# DIY_Keyboard_V1_2.net
KiCad netlist of a schematic drawn in EAGLE
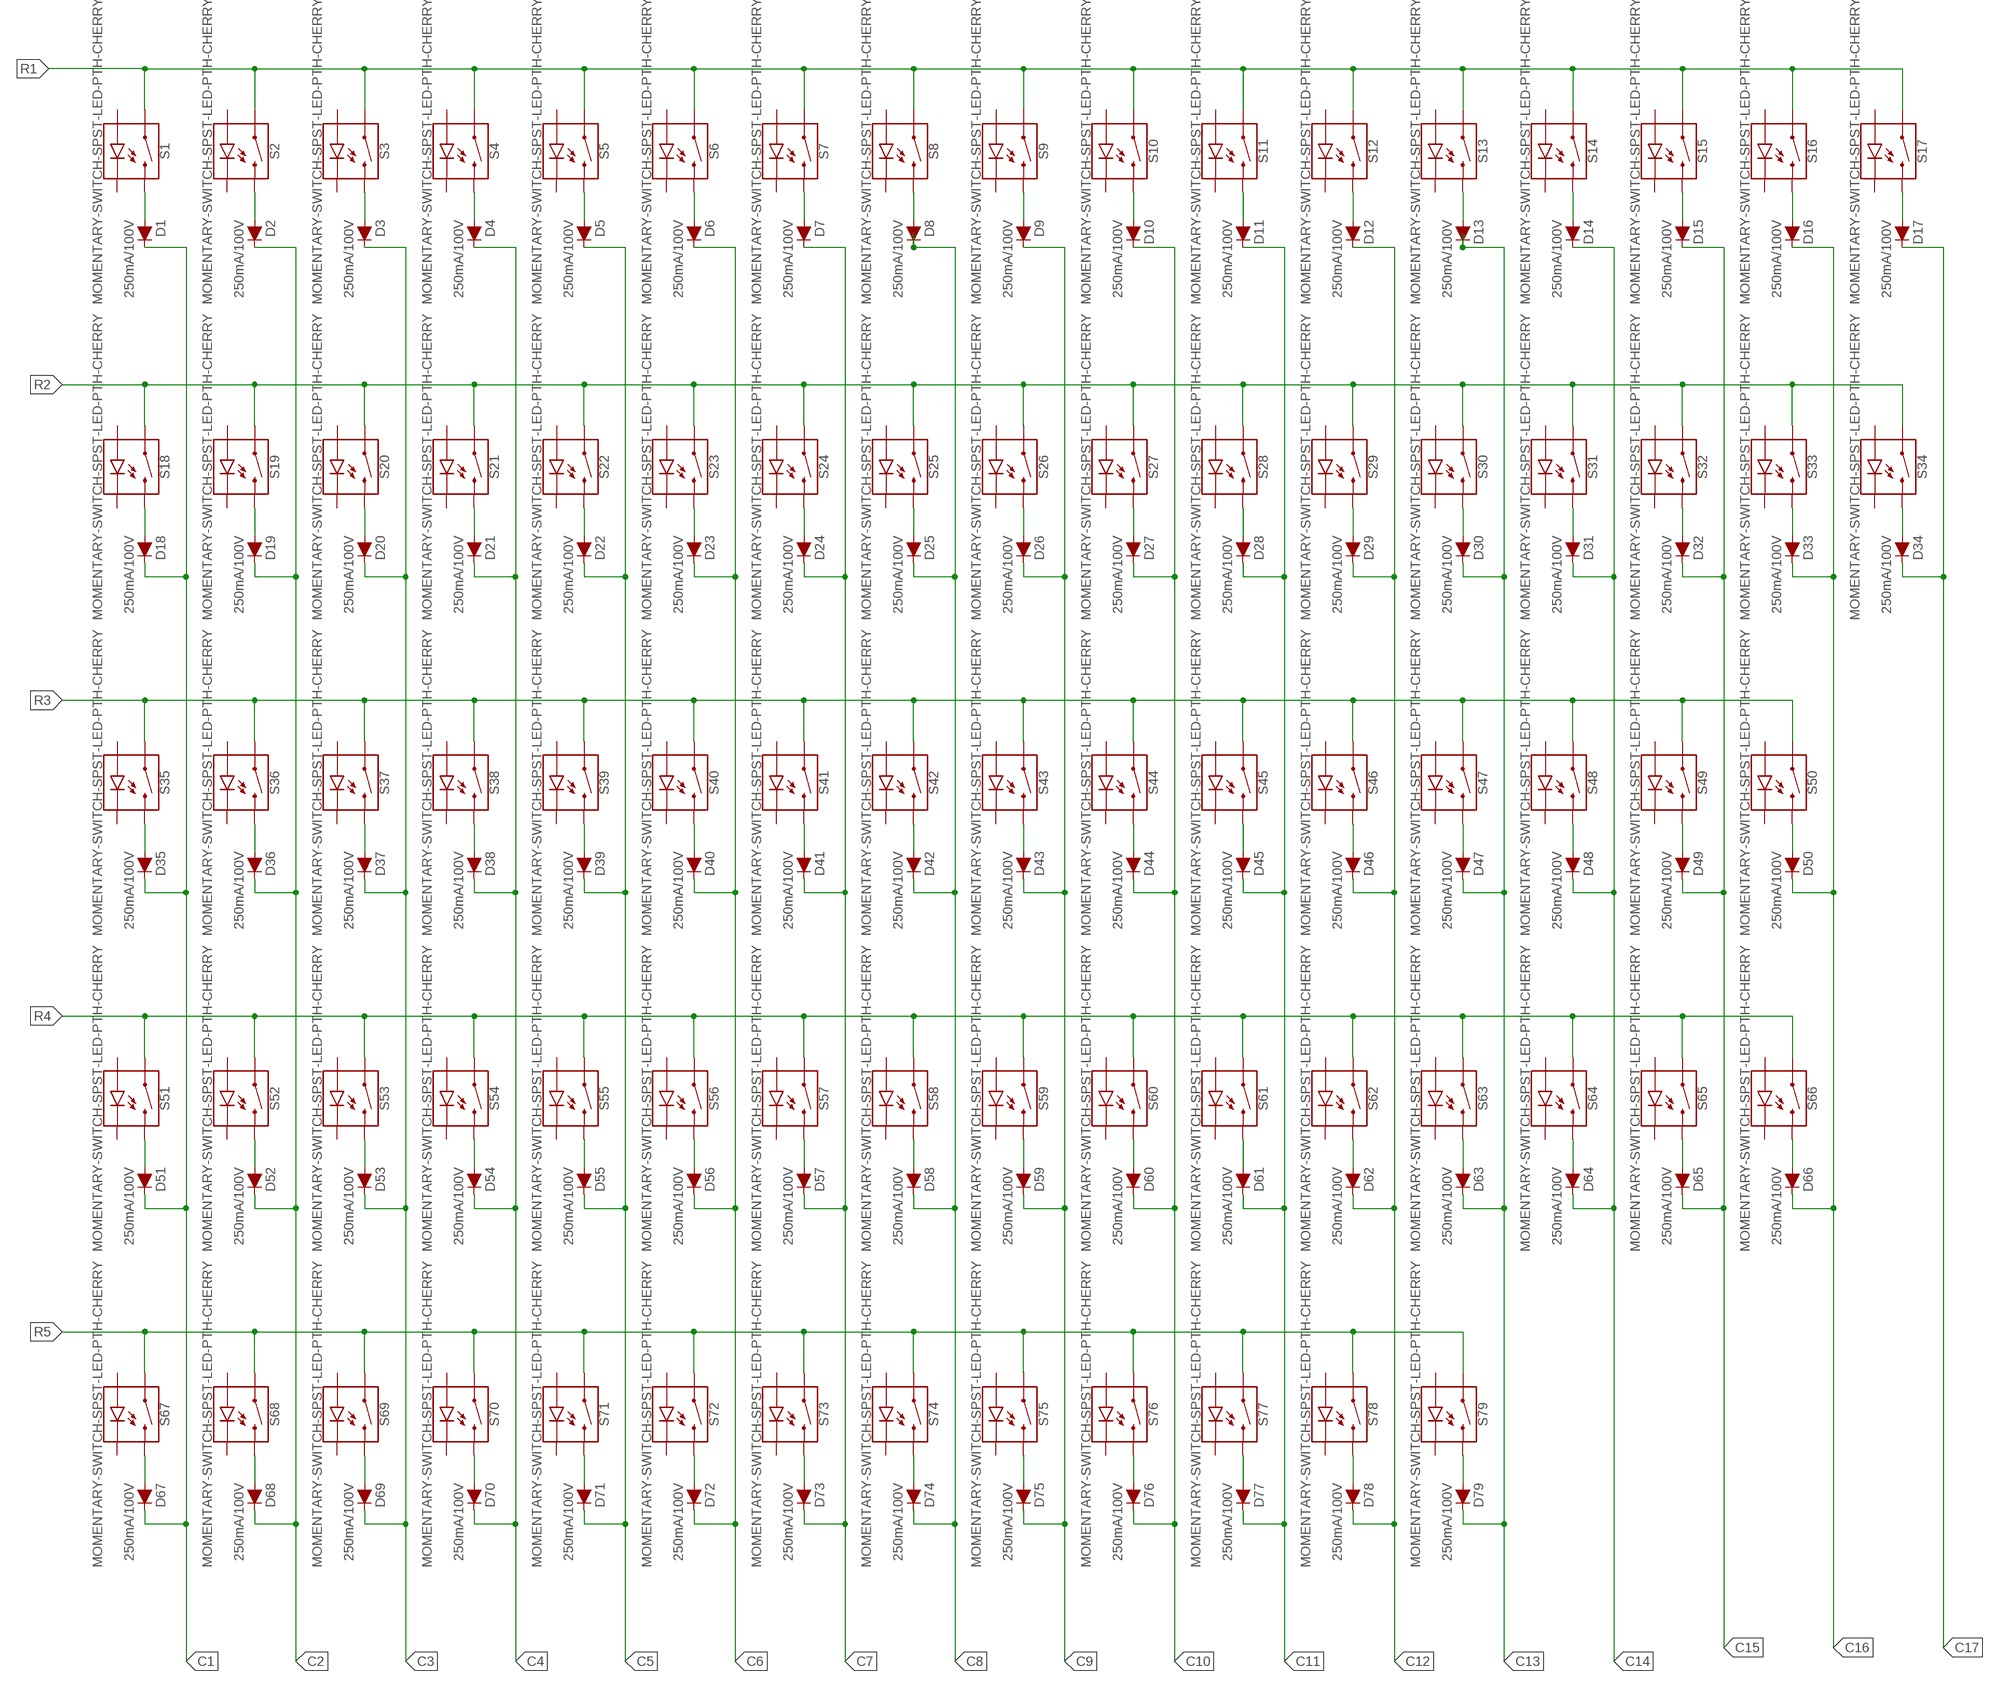
[diagram p0: schematic, sheet 1, part 1 of 2]
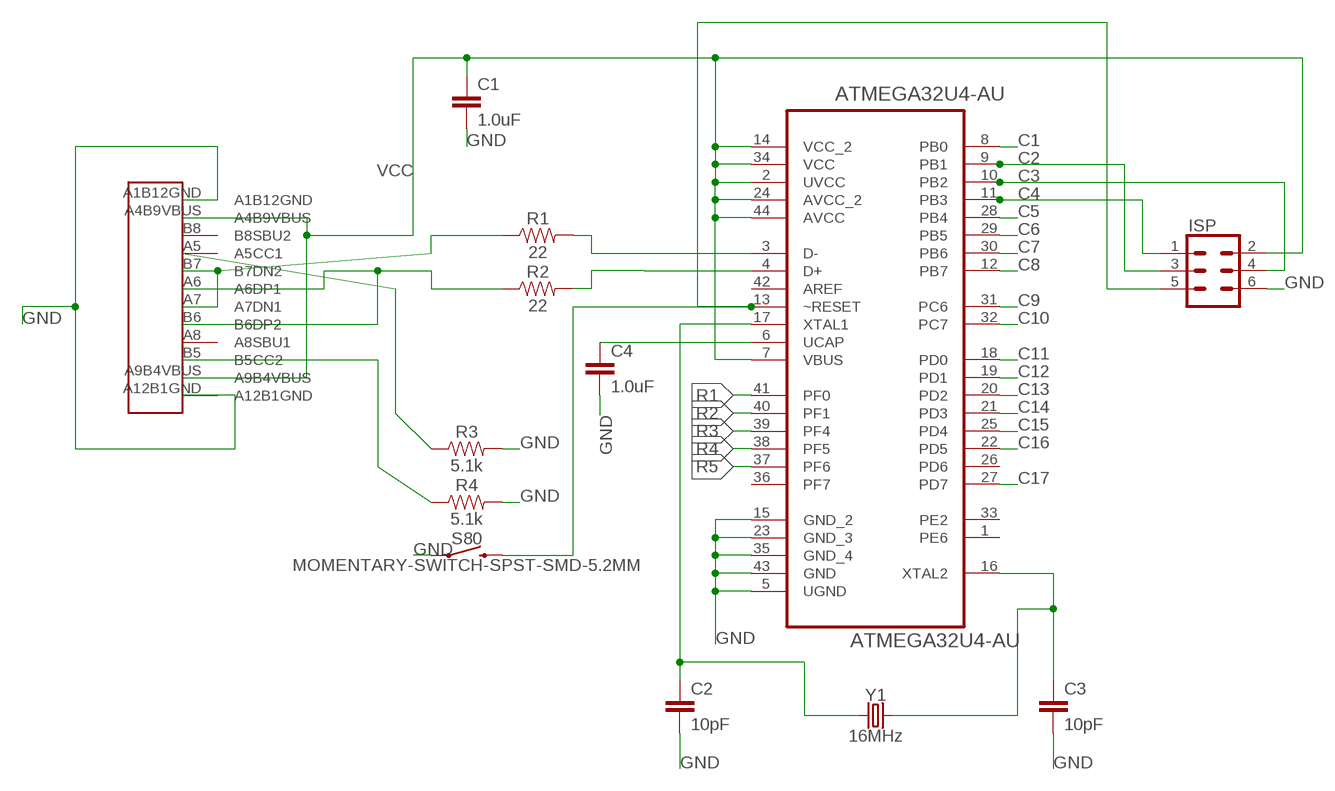
[diagram p1: schematic, sheet 1, part 2 of 2]

(export (version "E")
  (design (tool "Eeschema 10.0.6"))
  (components
    (comp (ref "ATMEGA32U4-AU")
      (value "ATMEGA32U4-AU")
      (footprint "eagle-import:QFP80P1200X1200X120-44N")
      (fields (field (name "MF") "Microchip"))
      (libsource (lib "eagle-import") (part "ATMEGA32U4-AU"))
    )
    (comp (ref "C1")
      (value "1.0uF")
      (footprint "eagle-import:0603")
      (libsource (lib "eagle-import") (part "1.0UF-0603-16V-10%"))
    )
    (comp (ref "C2")
      (value "10pF")
      (footprint "eagle-import:0603")
      (libsource (lib "eagle-import") (part "10PF-0603-50V-5%"))
    )
    (comp (ref "C3")
      (value "10pF")
      (footprint "eagle-import:0603")
      (libsource (lib "eagle-import") (part "10PF-0603-50V-5%"))
    )
    (comp (ref "C4")
      (value "1.0uF")
      (footprint "eagle-import:0603")
      (libsource (lib "eagle-import") (part "1.0UF-0603-16V-10%"))
    )
    (comp (ref "D1")
      (value "250mA/100V")
      (footprint "eagle-import:SOD-323")
      (libsource (lib "eagle-import") (part "DIODE-BAS16J"))
    )
    (comp (ref "D2")
      (value "250mA/100V")
      (footprint "eagle-import:SOD-323")
      (libsource (lib "eagle-import") (part "DIODE-BAS16J"))
    )
    (comp (ref "D3")
      (value "250mA/100V")
      (footprint "eagle-import:SOD-323")
      (libsource (lib "eagle-import") (part "DIODE-BAS16J"))
    )
    (comp (ref "D4")
      (value "250mA/100V")
      (footprint "eagle-import:SOD-323")
      (libsource (lib "eagle-import") (part "DIODE-BAS16J"))
    )
    (comp (ref "D5")
      (value "250mA/100V")
      (footprint "eagle-import:SOD-323")
      (libsource (lib "eagle-import") (part "DIODE-BAS16J"))
    )
    (comp (ref "D6")
      (value "250mA/100V")
      (footprint "eagle-import:SOD-323")
      (libsource (lib "eagle-import") (part "DIODE-BAS16J"))
    )
    (comp (ref "D7")
      (value "250mA/100V")
      (footprint "eagle-import:SOD-323")
      (libsource (lib "eagle-import") (part "DIODE-BAS16J"))
    )
    (comp (ref "D8")
      (value "250mA/100V")
      (footprint "eagle-import:SOD-323")
      (libsource (lib "eagle-import") (part "DIODE-BAS16J"))
    )
    (comp (ref "D9")
      (value "250mA/100V")
      (footprint "eagle-import:SOD-323")
      (libsource (lib "eagle-import") (part "DIODE-BAS16J"))
    )
    (comp (ref "D10")
      (value "250mA/100V")
      (footprint "eagle-import:SOD-323")
      (libsource (lib "eagle-import") (part "DIODE-BAS16J"))
    )
    (comp (ref "D11")
      (value "250mA/100V")
      (footprint "eagle-import:SOD-323")
      (libsource (lib "eagle-import") (part "DIODE-BAS16J"))
    )
    (comp (ref "D12")
      (value "250mA/100V")
      (footprint "eagle-import:SOD-323")
      (libsource (lib "eagle-import") (part "DIODE-BAS16J"))
    )
    (comp (ref "D13")
      (value "250mA/100V")
      (footprint "eagle-import:SOD-323")
      (libsource (lib "eagle-import") (part "DIODE-BAS16J"))
    )
    (comp (ref "D14")
      (value "250mA/100V")
      (footprint "eagle-import:SOD-323")
      (libsource (lib "eagle-import") (part "DIODE-BAS16J"))
    )
    (comp (ref "D15")
      (value "250mA/100V")
      (footprint "eagle-import:SOD-323")
      (libsource (lib "eagle-import") (part "DIODE-BAS16J"))
    )
    (comp (ref "D16")
      (value "250mA/100V")
      (footprint "eagle-import:SOD-323")
      (libsource (lib "eagle-import") (part "DIODE-BAS16J"))
    )
    (comp (ref "D17")
      (value "250mA/100V")
      (footprint "eagle-import:SOD-323")
      (libsource (lib "eagle-import") (part "DIODE-BAS16J"))
    )
    (comp (ref "D18")
      (value "250mA/100V")
      (footprint "eagle-import:SOD-323")
      (libsource (lib "eagle-import") (part "DIODE-BAS16J"))
    )
    (comp (ref "D19")
      (value "250mA/100V")
      (footprint "eagle-import:SOD-323")
      (libsource (lib "eagle-import") (part "DIODE-BAS16J"))
    )
    (comp (ref "D20")
      (value "250mA/100V")
      (footprint "eagle-import:SOD-323")
      (libsource (lib "eagle-import") (part "DIODE-BAS16J"))
    )
    (comp (ref "D21")
      (value "250mA/100V")
      (footprint "eagle-import:SOD-323")
      (libsource (lib "eagle-import") (part "DIODE-BAS16J"))
    )
    (comp (ref "D22")
      (value "250mA/100V")
      (footprint "eagle-import:SOD-323")
      (libsource (lib "eagle-import") (part "DIODE-BAS16J"))
    )
    (comp (ref "D23")
      (value "250mA/100V")
      (footprint "eagle-import:SOD-323")
      (libsource (lib "eagle-import") (part "DIODE-BAS16J"))
    )
    (comp (ref "D24")
      (value "250mA/100V")
      (footprint "eagle-import:SOD-323")
      (libsource (lib "eagle-import") (part "DIODE-BAS16J"))
    )
    (comp (ref "D25")
      (value "250mA/100V")
      (footprint "eagle-import:SOD-323")
      (libsource (lib "eagle-import") (part "DIODE-BAS16J"))
    )
    (comp (ref "D26")
      (value "250mA/100V")
      (footprint "eagle-import:SOD-323")
      (libsource (lib "eagle-import") (part "DIODE-BAS16J"))
    )
    (comp (ref "D27")
      (value "250mA/100V")
      (footprint "eagle-import:SOD-323")
      (libsource (lib "eagle-import") (part "DIODE-BAS16J"))
    )
    (comp (ref "D28")
      (value "250mA/100V")
      (footprint "eagle-import:SOD-323")
      (libsource (lib "eagle-import") (part "DIODE-BAS16J"))
    )
    (comp (ref "D29")
      (value "250mA/100V")
      (footprint "eagle-import:SOD-323")
      (libsource (lib "eagle-import") (part "DIODE-BAS16J"))
    )
    (comp (ref "D30")
      (value "250mA/100V")
      (footprint "eagle-import:SOD-323")
      (libsource (lib "eagle-import") (part "DIODE-BAS16J"))
    )
    (comp (ref "D31")
      (value "250mA/100V")
      (footprint "eagle-import:SOD-323")
      (libsource (lib "eagle-import") (part "DIODE-BAS16J"))
    )
    (comp (ref "D32")
      (value "250mA/100V")
      (footprint "eagle-import:SOD-323")
      (libsource (lib "eagle-import") (part "DIODE-BAS16J"))
    )
    (comp (ref "D33")
      (value "250mA/100V")
      (footprint "eagle-import:SOD-323")
      (libsource (lib "eagle-import") (part "DIODE-BAS16J"))
    )
    (comp (ref "D34")
      (value "250mA/100V")
      (footprint "eagle-import:SOD-323")
      (libsource (lib "eagle-import") (part "DIODE-BAS16J"))
    )
    (comp (ref "D35")
      (value "250mA/100V")
      (footprint "eagle-import:SOD-323")
      (libsource (lib "eagle-import") (part "DIODE-BAS16J"))
    )
    (comp (ref "D36")
      (value "250mA/100V")
      (footprint "eagle-import:SOD-323")
      (libsource (lib "eagle-import") (part "DIODE-BAS16J"))
    )
    (comp (ref "D37")
      (value "250mA/100V")
      (footprint "eagle-import:SOD-323")
      (libsource (lib "eagle-import") (part "DIODE-BAS16J"))
    )
    (comp (ref "D38")
      (value "250mA/100V")
      (footprint "eagle-import:SOD-323")
      (libsource (lib "eagle-import") (part "DIODE-BAS16J"))
    )
    (comp (ref "D39")
      (value "250mA/100V")
      (footprint "eagle-import:SOD-323")
      (libsource (lib "eagle-import") (part "DIODE-BAS16J"))
    )
    (comp (ref "D40")
      (value "250mA/100V")
      (footprint "eagle-import:SOD-323")
      (libsource (lib "eagle-import") (part "DIODE-BAS16J"))
    )
    (comp (ref "D41")
      (value "250mA/100V")
      (footprint "eagle-import:SOD-323")
      (libsource (lib "eagle-import") (part "DIODE-BAS16J"))
    )
    (comp (ref "D42")
      (value "250mA/100V")
      (footprint "eagle-import:SOD-323")
      (libsource (lib "eagle-import") (part "DIODE-BAS16J"))
    )
    (comp (ref "D43")
      (value "250mA/100V")
      (footprint "eagle-import:SOD-323")
      (libsource (lib "eagle-import") (part "DIODE-BAS16J"))
    )
    (comp (ref "D44")
      (value "250mA/100V")
      (footprint "eagle-import:SOD-323")
      (libsource (lib "eagle-import") (part "DIODE-BAS16J"))
    )
    (comp (ref "D45")
      (value "250mA/100V")
      (footprint "eagle-import:SOD-323")
      (libsource (lib "eagle-import") (part "DIODE-BAS16J"))
    )
    (comp (ref "D46")
      (value "250mA/100V")
      (footprint "eagle-import:SOD-323")
      (libsource (lib "eagle-import") (part "DIODE-BAS16J"))
    )
    (comp (ref "D47")
      (value "250mA/100V")
      (footprint "eagle-import:SOD-323")
      (libsource (lib "eagle-import") (part "DIODE-BAS16J"))
    )
    (comp (ref "D48")
      (value "250mA/100V")
      (footprint "eagle-import:SOD-323")
      (libsource (lib "eagle-import") (part "DIODE-BAS16J"))
    )
    (comp (ref "D49")
      (value "250mA/100V")
      (footprint "eagle-import:SOD-323")
      (libsource (lib "eagle-import") (part "DIODE-BAS16J"))
    )
    (comp (ref "D50")
      (value "250mA/100V")
      (footprint "eagle-import:SOD-323")
      (libsource (lib "eagle-import") (part "DIODE-BAS16J"))
    )
    (comp (ref "D51")
      (value "250mA/100V")
      (footprint "eagle-import:SOD-323")
      (libsource (lib "eagle-import") (part "DIODE-BAS16J"))
    )
    (comp (ref "D52")
      (value "250mA/100V")
      (footprint "eagle-import:SOD-323")
      (libsource (lib "eagle-import") (part "DIODE-BAS16J"))
    )
    (comp (ref "D53")
      (value "250mA/100V")
      (footprint "eagle-import:SOD-323")
      (libsource (lib "eagle-import") (part "DIODE-BAS16J"))
    )
    (comp (ref "D54")
      (value "250mA/100V")
      (footprint "eagle-import:SOD-323")
      (libsource (lib "eagle-import") (part "DIODE-BAS16J"))
    )
    (comp (ref "D55")
      (value "250mA/100V")
      (footprint "eagle-import:SOD-323")
      (libsource (lib "eagle-import") (part "DIODE-BAS16J"))
    )
    (comp (ref "D56")
      (value "250mA/100V")
      (footprint "eagle-import:SOD-323")
      (libsource (lib "eagle-import") (part "DIODE-BAS16J"))
    )
    (comp (ref "D57")
      (value "250mA/100V")
      (footprint "eagle-import:SOD-323")
      (libsource (lib "eagle-import") (part "DIODE-BAS16J"))
    )
    (comp (ref "D58")
      (value "250mA/100V")
      (footprint "eagle-import:SOD-323")
      (libsource (lib "eagle-import") (part "DIODE-BAS16J"))
    )
    (comp (ref "D59")
      (value "250mA/100V")
      (footprint "eagle-import:SOD-323")
      (libsource (lib "eagle-import") (part "DIODE-BAS16J"))
    )
    (comp (ref "D60")
      (value "250mA/100V")
      (footprint "eagle-import:SOD-323")
      (libsource (lib "eagle-import") (part "DIODE-BAS16J"))
    )
    (comp (ref "D61")
      (value "250mA/100V")
      (footprint "eagle-import:SOD-323")
      (libsource (lib "eagle-import") (part "DIODE-BAS16J"))
    )
    (comp (ref "D62")
      (value "250mA/100V")
      (footprint "eagle-import:SOD-323")
      (libsource (lib "eagle-import") (part "DIODE-BAS16J"))
    )
    (comp (ref "D63")
      (value "250mA/100V")
      (footprint "eagle-import:SOD-323")
      (libsource (lib "eagle-import") (part "DIODE-BAS16J"))
    )
    (comp (ref "D64")
      (value "250mA/100V")
      (footprint "eagle-import:SOD-323")
      (libsource (lib "eagle-import") (part "DIODE-BAS16J"))
    )
    (comp (ref "D65")
      (value "250mA/100V")
      (footprint "eagle-import:SOD-323")
      (libsource (lib "eagle-import") (part "DIODE-BAS16J"))
    )
    (comp (ref "D66")
      (value "250mA/100V")
      (footprint "eagle-import:SOD-323")
      (libsource (lib "eagle-import") (part "DIODE-BAS16J"))
    )
    (comp (ref "D67")
      (value "250mA/100V")
      (footprint "eagle-import:SOD-323")
      (libsource (lib "eagle-import") (part "DIODE-BAS16J"))
    )
    (comp (ref "D68")
      (value "250mA/100V")
      (footprint "eagle-import:SOD-323")
      (libsource (lib "eagle-import") (part "DIODE-BAS16J"))
    )
    (comp (ref "D69")
      (value "250mA/100V")
      (footprint "eagle-import:SOD-323")
      (libsource (lib "eagle-import") (part "DIODE-BAS16J"))
    )
    (comp (ref "D70")
      (value "250mA/100V")
      (footprint "eagle-import:SOD-323")
      (libsource (lib "eagle-import") (part "DIODE-BAS16J"))
    )
    (comp (ref "D71")
      (value "250mA/100V")
      (footprint "eagle-import:SOD-323")
      (libsource (lib "eagle-import") (part "DIODE-BAS16J"))
    )
    (comp (ref "D72")
      (value "250mA/100V")
      (footprint "eagle-import:SOD-323")
      (libsource (lib "eagle-import") (part "DIODE-BAS16J"))
    )
    (comp (ref "D73")
      (value "250mA/100V")
      (footprint "eagle-import:SOD-323")
      (libsource (lib "eagle-import") (part "DIODE-BAS16J"))
    )
    (comp (ref "D74")
      (value "250mA/100V")
      (footprint "eagle-import:SOD-323")
      (libsource (lib "eagle-import") (part "DIODE-BAS16J"))
    )
    (comp (ref "D75")
      (value "250mA/100V")
      (footprint "eagle-import:SOD-323")
      (libsource (lib "eagle-import") (part "DIODE-BAS16J"))
    )
    (comp (ref "D76")
      (value "250mA/100V")
      (footprint "eagle-import:SOD-323")
      (libsource (lib "eagle-import") (part "DIODE-BAS16J"))
    )
    (comp (ref "D77")
      (value "250mA/100V")
      (footprint "eagle-import:SOD-323")
      (libsource (lib "eagle-import") (part "DIODE-BAS16J"))
    )
    (comp (ref "D78")
      (value "250mA/100V")
      (footprint "eagle-import:SOD-323")
      (libsource (lib "eagle-import") (part "DIODE-BAS16J"))
    )
    (comp (ref "D79")
      (value "250mA/100V")
      (footprint "eagle-import:SOD-323")
      (libsource (lib "eagle-import") (part "DIODE-BAS16J"))
    )
    (comp (ref "ISP")
      (value "CONN_03X2FEMALE")
      (footprint "eagle-import:2X3")
      (libsource (lib "eagle-import") (part "CONN_03X2FEMALE"))
    )
    (comp (ref "R1")
      (value "22")
      (footprint "eagle-import:0603")
      (libsource (lib "eagle-import") (part "22OHM-0603-1/10W-1%"))
    )
    (comp (ref "R2")
      (value "22")
      (footprint "eagle-import:0603")
      (libsource (lib "eagle-import") (part "22OHM-0603-1/10W-1%"))
    )
    (comp (ref "R3")
      (value "5.1k")
      (footprint "eagle-import:0603")
      (libsource (lib "eagle-import") (part "56KOHM"))
    )
    (comp (ref "R4")
      (value "5.1k")
      (footprint "eagle-import:0603")
      (libsource (lib "eagle-import") (part "56KOHM"))
    )
    (comp (ref "S1")
      (value "MOMENTARY-SWITCH-SPST-LED-PTH-CHERRY")
      (footprint "eagle-import:CHERRY-MX-LED")
      (libsource (lib "eagle-import") (part "MOMENTARY-SWITCH-SPST-LED-PTH-CHERRY"))
    )
    (comp (ref "S2")
      (value "MOMENTARY-SWITCH-SPST-LED-PTH-CHERRY")
      (footprint "eagle-import:CHERRY-MX-LED")
      (libsource (lib "eagle-import") (part "MOMENTARY-SWITCH-SPST-LED-PTH-CHERRY"))
    )
    (comp (ref "S3")
      (value "MOMENTARY-SWITCH-SPST-LED-PTH-CHERRY")
      (footprint "eagle-import:CHERRY-MX-LED")
      (libsource (lib "eagle-import") (part "MOMENTARY-SWITCH-SPST-LED-PTH-CHERRY"))
    )
    (comp (ref "S4")
      (value "MOMENTARY-SWITCH-SPST-LED-PTH-CHERRY")
      (footprint "eagle-import:CHERRY-MX-LED")
      (libsource (lib "eagle-import") (part "MOMENTARY-SWITCH-SPST-LED-PTH-CHERRY"))
    )
    (comp (ref "S5")
      (value "MOMENTARY-SWITCH-SPST-LED-PTH-CHERRY")
      (footprint "eagle-import:CHERRY-MX-LED")
      (libsource (lib "eagle-import") (part "MOMENTARY-SWITCH-SPST-LED-PTH-CHERRY"))
    )
    (comp (ref "S6")
      (value "MOMENTARY-SWITCH-SPST-LED-PTH-CHERRY")
      (footprint "eagle-import:CHERRY-MX-LED")
      (libsource (lib "eagle-import") (part "MOMENTARY-SWITCH-SPST-LED-PTH-CHERRY"))
    )
    (comp (ref "S7")
      (value "MOMENTARY-SWITCH-SPST-LED-PTH-CHERRY")
      (footprint "eagle-import:CHERRY-MX-LED")
      (libsource (lib "eagle-import") (part "MOMENTARY-SWITCH-SPST-LED-PTH-CHERRY"))
    )
    (comp (ref "S8")
      (value "MOMENTARY-SWITCH-SPST-LED-PTH-CHERRY")
      (footprint "eagle-import:CHERRY-MX-LED")
      (libsource (lib "eagle-import") (part "MOMENTARY-SWITCH-SPST-LED-PTH-CHERRY"))
    )
    (comp (ref "S9")
      (value "MOMENTARY-SWITCH-SPST-LED-PTH-CHERRY")
      (footprint "eagle-import:CHERRY-MX-LED")
      (libsource (lib "eagle-import") (part "MOMENTARY-SWITCH-SPST-LED-PTH-CHERRY"))
    )
    (comp (ref "S10")
      (value "MOMENTARY-SWITCH-SPST-LED-PTH-CHERRY")
      (footprint "eagle-import:CHERRY-MX-LED")
      (libsource (lib "eagle-import") (part "MOMENTARY-SWITCH-SPST-LED-PTH-CHERRY"))
    )
    (comp (ref "S11")
      (value "MOMENTARY-SWITCH-SPST-LED-PTH-CHERRY")
      (footprint "eagle-import:CHERRY-MX-LED")
      (libsource (lib "eagle-import") (part "MOMENTARY-SWITCH-SPST-LED-PTH-CHERRY"))
    )
    (comp (ref "S12")
      (value "MOMENTARY-SWITCH-SPST-LED-PTH-CHERRY")
      (footprint "eagle-import:CHERRY-MX-LED")
      (libsource (lib "eagle-import") (part "MOMENTARY-SWITCH-SPST-LED-PTH-CHERRY"))
    )
    (comp (ref "S13")
      (value "MOMENTARY-SWITCH-SPST-LED-PTH-CHERRY")
      (footprint "eagle-import:CHERRY-MX-LED")
      (libsource (lib "eagle-import") (part "MOMENTARY-SWITCH-SPST-LED-PTH-CHERRY"))
    )
    (comp (ref "S14")
      (value "MOMENTARY-SWITCH-SPST-LED-PTH-CHERRY")
      (footprint "eagle-import:CHERRY-MX-LED")
      (libsource (lib "eagle-import") (part "MOMENTARY-SWITCH-SPST-LED-PTH-CHERRY"))
    )
    (comp (ref "S15")
      (value "MOMENTARY-SWITCH-SPST-LED-PTH-CHERRY")
      (footprint "eagle-import:CHERRY-MX-LED")
      (libsource (lib "eagle-import") (part "MOMENTARY-SWITCH-SPST-LED-PTH-CHERRY"))
    )
    (comp (ref "S16")
      (value "MOMENTARY-SWITCH-SPST-LED-PTH-CHERRY")
      (footprint "eagle-import:CHERRY-MX-LED")
      (libsource (lib "eagle-import") (part "MOMENTARY-SWITCH-SPST-LED-PTH-CHERRY"))
    )
    (comp (ref "S17")
      (value "MOMENTARY-SWITCH-SPST-LED-PTH-CHERRY")
      (footprint "eagle-import:CHERRY-MX-LED")
      (libsource (lib "eagle-import") (part "MOMENTARY-SWITCH-SPST-LED-PTH-CHERRY"))
    )
    (comp (ref "S18")
      (value "MOMENTARY-SWITCH-SPST-LED-PTH-CHERRY")
      (footprint "eagle-import:CHERRY-MX-LED")
      (libsource (lib "eagle-import") (part "MOMENTARY-SWITCH-SPST-LED-PTH-CHERRY"))
    )
    (comp (ref "S19")
      (value "MOMENTARY-SWITCH-SPST-LED-PTH-CHERRY")
      (footprint "eagle-import:CHERRY-MX-LED")
      (libsource (lib "eagle-import") (part "MOMENTARY-SWITCH-SPST-LED-PTH-CHERRY"))
    )
    (comp (ref "S20")
      (value "MOMENTARY-SWITCH-SPST-LED-PTH-CHERRY")
      (footprint "eagle-import:CHERRY-MX-LED")
      (libsource (lib "eagle-import") (part "MOMENTARY-SWITCH-SPST-LED-PTH-CHERRY"))
    )
    (comp (ref "S21")
      (value "MOMENTARY-SWITCH-SPST-LED-PTH-CHERRY")
      (footprint "eagle-import:CHERRY-MX-LED")
      (libsource (lib "eagle-import") (part "MOMENTARY-SWITCH-SPST-LED-PTH-CHERRY"))
    )
    (comp (ref "S22")
      (value "MOMENTARY-SWITCH-SPST-LED-PTH-CHERRY")
      (footprint "eagle-import:CHERRY-MX-LED")
      (libsource (lib "eagle-import") (part "MOMENTARY-SWITCH-SPST-LED-PTH-CHERRY"))
    )
    (comp (ref "S23")
      (value "MOMENTARY-SWITCH-SPST-LED-PTH-CHERRY")
      (footprint "eagle-import:CHERRY-MX-LED")
      (libsource (lib "eagle-import") (part "MOMENTARY-SWITCH-SPST-LED-PTH-CHERRY"))
    )
    (comp (ref "S24")
      (value "MOMENTARY-SWITCH-SPST-LED-PTH-CHERRY")
      (footprint "eagle-import:CHERRY-MX-LED")
      (libsource (lib "eagle-import") (part "MOMENTARY-SWITCH-SPST-LED-PTH-CHERRY"))
    )
    (comp (ref "S25")
      (value "MOMENTARY-SWITCH-SPST-LED-PTH-CHERRY")
      (footprint "eagle-import:CHERRY-MX-LED")
      (libsource (lib "eagle-import") (part "MOMENTARY-SWITCH-SPST-LED-PTH-CHERRY"))
    )
    (comp (ref "S26")
      (value "MOMENTARY-SWITCH-SPST-LED-PTH-CHERRY")
      (footprint "eagle-import:CHERRY-MX-LED")
      (libsource (lib "eagle-import") (part "MOMENTARY-SWITCH-SPST-LED-PTH-CHERRY"))
    )
    (comp (ref "S27")
      (value "MOMENTARY-SWITCH-SPST-LED-PTH-CHERRY")
      (footprint "eagle-import:CHERRY-MX-LED")
      (libsource (lib "eagle-import") (part "MOMENTARY-SWITCH-SPST-LED-PTH-CHERRY"))
    )
    (comp (ref "S28")
      (value "MOMENTARY-SWITCH-SPST-LED-PTH-CHERRY")
      (footprint "eagle-import:CHERRY-MX-LED")
      (libsource (lib "eagle-import") (part "MOMENTARY-SWITCH-SPST-LED-PTH-CHERRY"))
    )
    (comp (ref "S29")
      (value "MOMENTARY-SWITCH-SPST-LED-PTH-CHERRY")
      (footprint "eagle-import:CHERRY-MX-LED")
      (libsource (lib "eagle-import") (part "MOMENTARY-SWITCH-SPST-LED-PTH-CHERRY"))
    )
    (comp (ref "S30")
      (value "MOMENTARY-SWITCH-SPST-LED-PTH-CHERRY")
      (footprint "eagle-import:CHERRY-MX-LED")
      (libsource (lib "eagle-import") (part "MOMENTARY-SWITCH-SPST-LED-PTH-CHERRY"))
    )
    (comp (ref "S31")
      (value "MOMENTARY-SWITCH-SPST-LED-PTH-CHERRY")
      (footprint "eagle-import:CHERRY-MX-LED")
      (libsource (lib "eagle-import") (part "MOMENTARY-SWITCH-SPST-LED-PTH-CHERRY"))
    )
    (comp (ref "S32")
      (value "MOMENTARY-SWITCH-SPST-LED-PTH-CHERRY")
      (footprint "eagle-import:CHERRY-MX-LED")
      (libsource (lib "eagle-import") (part "MOMENTARY-SWITCH-SPST-LED-PTH-CHERRY"))
    )
    (comp (ref "S33")
      (value "MOMENTARY-SWITCH-SPST-LED-PTH-CHERRY")
      (footprint "eagle-import:CHERRY-MX-LED")
      (libsource (lib "eagle-import") (part "MOMENTARY-SWITCH-SPST-LED-PTH-CHERRY"))
    )
    (comp (ref "S34")
      (value "MOMENTARY-SWITCH-SPST-LED-PTH-CHERRY")
      (footprint "eagle-import:CHERRY-MX-LED")
      (libsource (lib "eagle-import") (part "MOMENTARY-SWITCH-SPST-LED-PTH-CHERRY"))
    )
    (comp (ref "S35")
      (value "MOMENTARY-SWITCH-SPST-LED-PTH-CHERRY")
      (footprint "eagle-import:CHERRY-MX-LED")
      (libsource (lib "eagle-import") (part "MOMENTARY-SWITCH-SPST-LED-PTH-CHERRY"))
    )
    (comp (ref "S36")
      (value "MOMENTARY-SWITCH-SPST-LED-PTH-CHERRY")
      (footprint "eagle-import:CHERRY-MX-LED")
      (libsource (lib "eagle-import") (part "MOMENTARY-SWITCH-SPST-LED-PTH-CHERRY"))
    )
    (comp (ref "S37")
      (value "MOMENTARY-SWITCH-SPST-LED-PTH-CHERRY")
      (footprint "eagle-import:CHERRY-MX-LED")
      (libsource (lib "eagle-import") (part "MOMENTARY-SWITCH-SPST-LED-PTH-CHERRY"))
    )
    (comp (ref "S38")
      (value "MOMENTARY-SWITCH-SPST-LED-PTH-CHERRY")
      (footprint "eagle-import:CHERRY-MX-LED")
      (libsource (lib "eagle-import") (part "MOMENTARY-SWITCH-SPST-LED-PTH-CHERRY"))
    )
    (comp (ref "S39")
      (value "MOMENTARY-SWITCH-SPST-LED-PTH-CHERRY")
      (footprint "eagle-import:CHERRY-MX-LED")
      (libsource (lib "eagle-import") (part "MOMENTARY-SWITCH-SPST-LED-PTH-CHERRY"))
    )
    (comp (ref "S40")
      (value "MOMENTARY-SWITCH-SPST-LED-PTH-CHERRY")
      (footprint "eagle-import:CHERRY-MX-LED")
      (libsource (lib "eagle-import") (part "MOMENTARY-SWITCH-SPST-LED-PTH-CHERRY"))
    )
    (comp (ref "S41")
      (value "MOMENTARY-SWITCH-SPST-LED-PTH-CHERRY")
      (footprint "eagle-import:CHERRY-MX-LED")
      (libsource (lib "eagle-import") (part "MOMENTARY-SWITCH-SPST-LED-PTH-CHERRY"))
    )
    (comp (ref "S42")
      (value "MOMENTARY-SWITCH-SPST-LED-PTH-CHERRY")
      (footprint "eagle-import:CHERRY-MX-LED")
      (libsource (lib "eagle-import") (part "MOMENTARY-SWITCH-SPST-LED-PTH-CHERRY"))
    )
    (comp (ref "S43")
      (value "MOMENTARY-SWITCH-SPST-LED-PTH-CHERRY")
      (footprint "eagle-import:CHERRY-MX-LED")
      (libsource (lib "eagle-import") (part "MOMENTARY-SWITCH-SPST-LED-PTH-CHERRY"))
    )
    (comp (ref "S44")
      (value "MOMENTARY-SWITCH-SPST-LED-PTH-CHERRY")
      (footprint "eagle-import:CHERRY-MX-LED")
      (libsource (lib "eagle-import") (part "MOMENTARY-SWITCH-SPST-LED-PTH-CHERRY"))
    )
    (comp (ref "S45")
      (value "MOMENTARY-SWITCH-SPST-LED-PTH-CHERRY")
      (footprint "eagle-import:CHERRY-MX-LED")
      (libsource (lib "eagle-import") (part "MOMENTARY-SWITCH-SPST-LED-PTH-CHERRY"))
    )
    (comp (ref "S46")
      (value "MOMENTARY-SWITCH-SPST-LED-PTH-CHERRY")
      (footprint "eagle-import:CHERRY-MX-LED")
      (libsource (lib "eagle-import") (part "MOMENTARY-SWITCH-SPST-LED-PTH-CHERRY"))
    )
    (comp (ref "S47")
      (value "MOMENTARY-SWITCH-SPST-LED-PTH-CHERRY")
      (footprint "eagle-import:CHERRY-MX-LED")
      (libsource (lib "eagle-import") (part "MOMENTARY-SWITCH-SPST-LED-PTH-CHERRY"))
    )
    (comp (ref "S48")
      (value "MOMENTARY-SWITCH-SPST-LED-PTH-CHERRY")
      (footprint "eagle-import:CHERRY-MX-LED")
      (libsource (lib "eagle-import") (part "MOMENTARY-SWITCH-SPST-LED-PTH-CHERRY"))
    )
    (comp (ref "S49")
      (value "MOMENTARY-SWITCH-SPST-LED-PTH-CHERRY")
      (footprint "eagle-import:CHERRY-MX-LED")
      (libsource (lib "eagle-import") (part "MOMENTARY-SWITCH-SPST-LED-PTH-CHERRY"))
    )
    (comp (ref "S50")
      (value "MOMENTARY-SWITCH-SPST-LED-PTH-CHERRY")
      (footprint "eagle-import:CHERRY-MX-LED")
      (libsource (lib "eagle-import") (part "MOMENTARY-SWITCH-SPST-LED-PTH-CHERRY"))
    )
    (comp (ref "S51")
      (value "MOMENTARY-SWITCH-SPST-LED-PTH-CHERRY")
      (footprint "eagle-import:CHERRY-MX-LED")
      (libsource (lib "eagle-import") (part "MOMENTARY-SWITCH-SPST-LED-PTH-CHERRY"))
    )
    (comp (ref "S52")
      (value "MOMENTARY-SWITCH-SPST-LED-PTH-CHERRY")
      (footprint "eagle-import:CHERRY-MX-LED")
      (libsource (lib "eagle-import") (part "MOMENTARY-SWITCH-SPST-LED-PTH-CHERRY"))
    )
    (comp (ref "S53")
      (value "MOMENTARY-SWITCH-SPST-LED-PTH-CHERRY")
      (footprint "eagle-import:CHERRY-MX-LED")
      (libsource (lib "eagle-import") (part "MOMENTARY-SWITCH-SPST-LED-PTH-CHERRY"))
    )
    (comp (ref "S54")
      (value "MOMENTARY-SWITCH-SPST-LED-PTH-CHERRY")
      (footprint "eagle-import:CHERRY-MX-LED")
      (libsource (lib "eagle-import") (part "MOMENTARY-SWITCH-SPST-LED-PTH-CHERRY"))
    )
    (comp (ref "S55")
      (value "MOMENTARY-SWITCH-SPST-LED-PTH-CHERRY")
      (footprint "eagle-import:CHERRY-MX-LED")
      (libsource (lib "eagle-import") (part "MOMENTARY-SWITCH-SPST-LED-PTH-CHERRY"))
    )
    (comp (ref "S56")
      (value "MOMENTARY-SWITCH-SPST-LED-PTH-CHERRY")
      (footprint "eagle-import:CHERRY-MX-LED")
      (libsource (lib "eagle-import") (part "MOMENTARY-SWITCH-SPST-LED-PTH-CHERRY"))
    )
    (comp (ref "S57")
      (value "MOMENTARY-SWITCH-SPST-LED-PTH-CHERRY")
      (footprint "eagle-import:CHERRY-MX-LED")
      (libsource (lib "eagle-import") (part "MOMENTARY-SWITCH-SPST-LED-PTH-CHERRY"))
    )
    (comp (ref "S58")
      (value "MOMENTARY-SWITCH-SPST-LED-PTH-CHERRY")
      (footprint "eagle-import:CHERRY-MX-LED")
      (libsource (lib "eagle-import") (part "MOMENTARY-SWITCH-SPST-LED-PTH-CHERRY"))
    )
    (comp (ref "S59")
      (value "MOMENTARY-SWITCH-SPST-LED-PTH-CHERRY")
      (footprint "eagle-import:CHERRY-MX-LED")
      (libsource (lib "eagle-import") (part "MOMENTARY-SWITCH-SPST-LED-PTH-CHERRY"))
    )
    (comp (ref "S60")
      (value "MOMENTARY-SWITCH-SPST-LED-PTH-CHERRY")
      (footprint "eagle-import:CHERRY-MX-LED")
      (libsource (lib "eagle-import") (part "MOMENTARY-SWITCH-SPST-LED-PTH-CHERRY"))
    )
    (comp (ref "S61")
      (value "MOMENTARY-SWITCH-SPST-LED-PTH-CHERRY")
      (footprint "eagle-import:CHERRY-MX-LED")
      (libsource (lib "eagle-import") (part "MOMENTARY-SWITCH-SPST-LED-PTH-CHERRY"))
    )
    (comp (ref "S62")
      (value "MOMENTARY-SWITCH-SPST-LED-PTH-CHERRY")
      (footprint "eagle-import:CHERRY-MX-LED")
      (libsource (lib "eagle-import") (part "MOMENTARY-SWITCH-SPST-LED-PTH-CHERRY"))
    )
    (comp (ref "S63")
      (value "MOMENTARY-SWITCH-SPST-LED-PTH-CHERRY")
      (footprint "eagle-import:CHERRY-MX-LED")
      (libsource (lib "eagle-import") (part "MOMENTARY-SWITCH-SPST-LED-PTH-CHERRY"))
    )
    (comp (ref "S64")
      (value "MOMENTARY-SWITCH-SPST-LED-PTH-CHERRY")
      (footprint "eagle-import:CHERRY-MX-LED")
      (libsource (lib "eagle-import") (part "MOMENTARY-SWITCH-SPST-LED-PTH-CHERRY"))
    )
    (comp (ref "S65")
      (value "MOMENTARY-SWITCH-SPST-LED-PTH-CHERRY")
      (footprint "eagle-import:CHERRY-MX-LED")
      (libsource (lib "eagle-import") (part "MOMENTARY-SWITCH-SPST-LED-PTH-CHERRY"))
    )
    (comp (ref "S66")
      (value "MOMENTARY-SWITCH-SPST-LED-PTH-CHERRY")
      (footprint "eagle-import:CHERRY-MX-LED")
      (libsource (lib "eagle-import") (part "MOMENTARY-SWITCH-SPST-LED-PTH-CHERRY"))
    )
    (comp (ref "S67")
      (value "MOMENTARY-SWITCH-SPST-LED-PTH-CHERRY")
      (footprint "eagle-import:CHERRY-MX-LED")
      (libsource (lib "eagle-import") (part "MOMENTARY-SWITCH-SPST-LED-PTH-CHERRY"))
    )
    (comp (ref "S68")
      (value "MOMENTARY-SWITCH-SPST-LED-PTH-CHERRY")
      (footprint "eagle-import:CHERRY-MX-LED")
      (libsource (lib "eagle-import") (part "MOMENTARY-SWITCH-SPST-LED-PTH-CHERRY"))
    )
    (comp (ref "S69")
      (value "MOMENTARY-SWITCH-SPST-LED-PTH-CHERRY")
      (footprint "eagle-import:CHERRY-MX-LED")
      (libsource (lib "eagle-import") (part "MOMENTARY-SWITCH-SPST-LED-PTH-CHERRY"))
    )
    (comp (ref "S70")
      (value "MOMENTARY-SWITCH-SPST-LED-PTH-CHERRY")
      (footprint "eagle-import:CHERRY-MX-LED")
      (libsource (lib "eagle-import") (part "MOMENTARY-SWITCH-SPST-LED-PTH-CHERRY"))
    )
    (comp (ref "S71")
      (value "MOMENTARY-SWITCH-SPST-LED-PTH-CHERRY")
      (footprint "eagle-import:CHERRY-MX-LED")
      (libsource (lib "eagle-import") (part "MOMENTARY-SWITCH-SPST-LED-PTH-CHERRY"))
    )
    (comp (ref "S72")
      (value "MOMENTARY-SWITCH-SPST-LED-PTH-CHERRY")
      (footprint "eagle-import:CHERRY-MX-LED")
      (libsource (lib "eagle-import") (part "MOMENTARY-SWITCH-SPST-LED-PTH-CHERRY"))
    )
    (comp (ref "S73")
      (value "MOMENTARY-SWITCH-SPST-LED-PTH-CHERRY")
      (footprint "eagle-import:CHERRY-MX-LED")
      (libsource (lib "eagle-import") (part "MOMENTARY-SWITCH-SPST-LED-PTH-CHERRY"))
    )
    (comp (ref "S74")
      (value "MOMENTARY-SWITCH-SPST-LED-PTH-CHERRY")
      (footprint "eagle-import:CHERRY-MX-LED")
      (libsource (lib "eagle-import") (part "MOMENTARY-SWITCH-SPST-LED-PTH-CHERRY"))
    )
    (comp (ref "S75")
      (value "MOMENTARY-SWITCH-SPST-LED-PTH-CHERRY")
      (footprint "eagle-import:CHERRY-MX-LED")
      (libsource (lib "eagle-import") (part "MOMENTARY-SWITCH-SPST-LED-PTH-CHERRY"))
    )
    (comp (ref "S76")
      (value "MOMENTARY-SWITCH-SPST-LED-PTH-CHERRY")
      (footprint "eagle-import:CHERRY-MX-LED")
      (libsource (lib "eagle-import") (part "MOMENTARY-SWITCH-SPST-LED-PTH-CHERRY"))
    )
    (comp (ref "S77")
      (value "MOMENTARY-SWITCH-SPST-LED-PTH-CHERRY")
      (footprint "eagle-import:CHERRY-MX-LED")
      (libsource (lib "eagle-import") (part "MOMENTARY-SWITCH-SPST-LED-PTH-CHERRY"))
    )
    (comp (ref "S78")
      (value "MOMENTARY-SWITCH-SPST-LED-PTH-CHERRY")
      (footprint "eagle-import:CHERRY-MX-LED")
      (libsource (lib "eagle-import") (part "MOMENTARY-SWITCH-SPST-LED-PTH-CHERRY"))
    )
    (comp (ref "S79")
      (value "MOMENTARY-SWITCH-SPST-LED-PTH-CHERRY")
      (footprint "eagle-import:CHERRY-MX-LED")
      (libsource (lib "eagle-import") (part "MOMENTARY-SWITCH-SPST-LED-PTH-CHERRY"))
    )
    (comp (ref "S80")
      (value "MOMENTARY-SWITCH-SPST-SMD-5.2MM")
      (footprint "eagle-import:TACTILE_SWITCH_SMD_5.2MM")
      (libsource (lib "eagle-import") (part "MOMENTARY-SWITCH-SPST-SMD-5.2MM"))
    )
    (comp (ref "U$1")
      (value "USB_TYPE_C")
      (footprint "eagle-import:USB_TYPE_C")
      (libsource (lib "eagle-import") (part "USB_TYPE_C"))
    )
    (comp (ref "Y1")
      (value "16MHz")
      (footprint "eagle-import:CRYSTAL-SMD-5X3.2-4PAD")
      (libsource (lib "eagle-import") (part "CRYSTAL-16MHZSMD-5X3.2"))
    )
  )
  (nets
    (net (code "1") (name "/GND") (class "Default")
      (node (ref "ATMEGA32U4-AU") (pin "15") (pinfunction "GND_2_15") (pintype "passive"))
      (node (ref "ATMEGA32U4-AU") (pin "23") (pinfunction "GND_3_23") (pintype "passive"))
      (node (ref "ATMEGA32U4-AU") (pin "35") (pinfunction "GND_4_35") (pintype "passive"))
      (node (ref "ATMEGA32U4-AU") (pin "43") (pinfunction "GND_43") (pintype "passive"))
      (node (ref "ATMEGA32U4-AU") (pin "5") (pinfunction "UGND_5") (pintype "passive"))
      (node (ref "C1") (pin "2") (pinfunction "2_2") (pintype "passive"))
      (node (ref "C2") (pin "2") (pinfunction "2_2") (pintype "passive"))
      (node (ref "C3") (pin "2") (pinfunction "2_2") (pintype "passive"))
      (node (ref "C4") (pin "2") (pinfunction "2_2") (pintype "passive"))
      (node (ref "ISP") (pin "6") (pinfunction "6_6") (pintype "bidirectional"))
      (node (ref "R3") (pin "2") (pinfunction "2_2") (pintype "passive"))
      (node (ref "R4") (pin "2") (pinfunction "2_2") (pintype "passive"))
      (node (ref "S80") (pin "1") (pinfunction "1_1") (pintype "passive"))
      (node (ref "U$1") (pin "A12B1GND") (pinfunction "A12B1GND_A12B1GND") (pintype "bidirectional"))
      (node (ref "U$1") (pin "A1B12GND") (pinfunction "A1B12GND_A1B12GND") (pintype "bidirectional"))
    )
    (net (code "2") (name "/VCC") (class "Default")
      (node (ref "ATMEGA32U4-AU") (pin "14") (pinfunction "VCC_2_14") (pintype "power_in"))
      (node (ref "ATMEGA32U4-AU") (pin "2") (pinfunction "UVCC_2") (pintype "power_in"))
      (node (ref "ATMEGA32U4-AU") (pin "24") (pinfunction "AVCC_2_24") (pintype "power_in"))
      (node (ref "ATMEGA32U4-AU") (pin "34") (pinfunction "VCC_34") (pintype "power_in"))
      (node (ref "ATMEGA32U4-AU") (pin "44") (pinfunction "AVCC_44") (pintype "power_in"))
      (node (ref "ATMEGA32U4-AU") (pin "7") (pinfunction "VBUS_7") (pintype "input"))
      (node (ref "C1") (pin "1") (pinfunction "1_1") (pintype "passive"))
      (node (ref "ISP") (pin "2") (pinfunction "2_2") (pintype "bidirectional"))
      (node (ref "U$1") (pin "A4B9VBUS") (pinfunction "A4B9VBUS_A4B9VBUS") (pintype "bidirectional"))
      (node (ref "U$1") (pin "A9B4VBUS") (pinfunction "A9B4VBUS_A9B4VBUS") (pintype "bidirectional"))
    )
    (net (code "3") (name "C1") (class "Default")
      (node (ref "ATMEGA32U4-AU") (pin "8") (pinfunction "PB0_8") (pintype "bidirectional"))
      (node (ref "D1") (pin "C") (pinfunction "C_C") (pintype "passive"))
      (node (ref "D18") (pin "C") (pinfunction "C_C") (pintype "passive"))
      (node (ref "D35") (pin "C") (pinfunction "C_C") (pintype "passive"))
      (node (ref "D51") (pin "C") (pinfunction "C_C") (pintype "passive"))
      (node (ref "D67") (pin "C") (pinfunction "C_C") (pintype "passive"))
    )
    (net (code "4") (name "C2") (class "Default")
      (node (ref "ATMEGA32U4-AU") (pin "9") (pinfunction "PB1_9") (pintype "bidirectional"))
      (node (ref "D19") (pin "C") (pinfunction "C_C") (pintype "passive"))
      (node (ref "D2") (pin "C") (pinfunction "C_C") (pintype "passive"))
      (node (ref "D36") (pin "C") (pinfunction "C_C") (pintype "passive"))
      (node (ref "D52") (pin "C") (pinfunction "C_C") (pintype "passive"))
      (node (ref "D68") (pin "C") (pinfunction "C_C") (pintype "passive"))
      (node (ref "ISP") (pin "3") (pinfunction "3_3") (pintype "bidirectional"))
    )
    (net (code "5") (name "C3") (class "Default")
      (node (ref "ATMEGA32U4-AU") (pin "10") (pinfunction "PB2_10") (pintype "bidirectional"))
      (node (ref "D20") (pin "C") (pinfunction "C_C") (pintype "passive"))
      (node (ref "D3") (pin "C") (pinfunction "C_C") (pintype "passive"))
      (node (ref "D37") (pin "C") (pinfunction "C_C") (pintype "passive"))
      (node (ref "D53") (pin "C") (pinfunction "C_C") (pintype "passive"))
      (node (ref "D69") (pin "C") (pinfunction "C_C") (pintype "passive"))
      (node (ref "ISP") (pin "4") (pinfunction "4_4") (pintype "bidirectional"))
    )
    (net (code "6") (name "C4") (class "Default")
      (node (ref "ATMEGA32U4-AU") (pin "11") (pinfunction "PB3_11") (pintype "bidirectional"))
      (node (ref "D21") (pin "C") (pinfunction "C_C") (pintype "passive"))
      (node (ref "D38") (pin "C") (pinfunction "C_C") (pintype "passive"))
      (node (ref "D4") (pin "C") (pinfunction "C_C") (pintype "passive"))
      (node (ref "D54") (pin "C") (pinfunction "C_C") (pintype "passive"))
      (node (ref "D70") (pin "C") (pinfunction "C_C") (pintype "passive"))
      (node (ref "ISP") (pin "1") (pinfunction "1_1") (pintype "bidirectional"))
    )
    (net (code "7") (name "C5") (class "Default")
      (node (ref "ATMEGA32U4-AU") (pin "28") (pinfunction "PB4_28") (pintype "bidirectional"))
      (node (ref "D22") (pin "C") (pinfunction "C_C") (pintype "passive"))
      (node (ref "D39") (pin "C") (pinfunction "C_C") (pintype "passive"))
      (node (ref "D5") (pin "C") (pinfunction "C_C") (pintype "passive"))
      (node (ref "D55") (pin "C") (pinfunction "C_C") (pintype "passive"))
      (node (ref "D71") (pin "C") (pinfunction "C_C") (pintype "passive"))
    )
    (net (code "8") (name "C6") (class "Default")
      (node (ref "ATMEGA32U4-AU") (pin "29") (pinfunction "PB5_29") (pintype "bidirectional"))
      (node (ref "D23") (pin "C") (pinfunction "C_C") (pintype "passive"))
      (node (ref "D40") (pin "C") (pinfunction "C_C") (pintype "passive"))
      (node (ref "D56") (pin "C") (pinfunction "C_C") (pintype "passive"))
      (node (ref "D6") (pin "C") (pinfunction "C_C") (pintype "passive"))
      (node (ref "D72") (pin "C") (pinfunction "C_C") (pintype "passive"))
    )
    (net (code "9") (name "C7") (class "Default")
      (node (ref "ATMEGA32U4-AU") (pin "30") (pinfunction "PB6_30") (pintype "bidirectional"))
      (node (ref "D24") (pin "C") (pinfunction "C_C") (pintype "passive"))
      (node (ref "D41") (pin "C") (pinfunction "C_C") (pintype "passive"))
      (node (ref "D57") (pin "C") (pinfunction "C_C") (pintype "passive"))
      (node (ref "D7") (pin "C") (pinfunction "C_C") (pintype "passive"))
      (node (ref "D73") (pin "C") (pinfunction "C_C") (pintype "passive"))
    )
    (net (code "10") (name "C8") (class "Default")
      (node (ref "ATMEGA32U4-AU") (pin "12") (pinfunction "PB7_12") (pintype "bidirectional"))
      (node (ref "D25") (pin "C") (pinfunction "C_C") (pintype "passive"))
      (node (ref "D42") (pin "C") (pinfunction "C_C") (pintype "passive"))
      (node (ref "D58") (pin "C") (pinfunction "C_C") (pintype "passive"))
      (node (ref "D74") (pin "C") (pinfunction "C_C") (pintype "passive"))
      (node (ref "D8") (pin "C") (pinfunction "C_C") (pintype "passive"))
    )
    (net (code "11") (name "C9") (class "Default")
      (node (ref "ATMEGA32U4-AU") (pin "31") (pinfunction "PC6_31") (pintype "bidirectional"))
      (node (ref "D26") (pin "C") (pinfunction "C_C") (pintype "passive"))
      (node (ref "D43") (pin "C") (pinfunction "C_C") (pintype "passive"))
      (node (ref "D59") (pin "C") (pinfunction "C_C") (pintype "passive"))
      (node (ref "D75") (pin "C") (pinfunction "C_C") (pintype "passive"))
      (node (ref "D9") (pin "C") (pinfunction "C_C") (pintype "passive"))
    )
    (net (code "12") (name "C10") (class "Default")
      (node (ref "ATMEGA32U4-AU") (pin "32") (pinfunction "PC7_32") (pintype "bidirectional"))
      (node (ref "D10") (pin "C") (pinfunction "C_C") (pintype "passive"))
      (node (ref "D27") (pin "C") (pinfunction "C_C") (pintype "passive"))
      (node (ref "D44") (pin "C") (pinfunction "C_C") (pintype "passive"))
      (node (ref "D60") (pin "C") (pinfunction "C_C") (pintype "passive"))
      (node (ref "D76") (pin "C") (pinfunction "C_C") (pintype "passive"))
    )
    (net (code "13") (name "C11") (class "Default")
      (node (ref "ATMEGA32U4-AU") (pin "18") (pinfunction "PD0_18") (pintype "bidirectional"))
      (node (ref "D11") (pin "C") (pinfunction "C_C") (pintype "passive"))
      (node (ref "D28") (pin "C") (pinfunction "C_C") (pintype "passive"))
      (node (ref "D45") (pin "C") (pinfunction "C_C") (pintype "passive"))
      (node (ref "D61") (pin "C") (pinfunction "C_C") (pintype "passive"))
      (node (ref "D77") (pin "C") (pinfunction "C_C") (pintype "passive"))
    )
    (net (code "14") (name "C12") (class "Default")
      (node (ref "ATMEGA32U4-AU") (pin "19") (pinfunction "PD1_19") (pintype "bidirectional"))
      (node (ref "D12") (pin "C") (pinfunction "C_C") (pintype "passive"))
      (node (ref "D29") (pin "C") (pinfunction "C_C") (pintype "passive"))
      (node (ref "D46") (pin "C") (pinfunction "C_C") (pintype "passive"))
      (node (ref "D62") (pin "C") (pinfunction "C_C") (pintype "passive"))
      (node (ref "D78") (pin "C") (pinfunction "C_C") (pintype "passive"))
    )
    (net (code "15") (name "C13") (class "Default")
      (node (ref "ATMEGA32U4-AU") (pin "20") (pinfunction "PD2_20") (pintype "bidirectional"))
      (node (ref "D13") (pin "C") (pinfunction "C_C") (pintype "passive"))
      (node (ref "D30") (pin "C") (pinfunction "C_C") (pintype "passive"))
      (node (ref "D47") (pin "C") (pinfunction "C_C") (pintype "passive"))
      (node (ref "D63") (pin "C") (pinfunction "C_C") (pintype "passive"))
      (node (ref "D79") (pin "C") (pinfunction "C_C") (pintype "passive"))
    )
    (net (code "16") (name "C14") (class "Default")
      (node (ref "ATMEGA32U4-AU") (pin "21") (pinfunction "PD3_21") (pintype "bidirectional"))
      (node (ref "D14") (pin "C") (pinfunction "C_C") (pintype "passive"))
      (node (ref "D31") (pin "C") (pinfunction "C_C") (pintype "passive"))
      (node (ref "D48") (pin "C") (pinfunction "C_C") (pintype "passive"))
      (node (ref "D64") (pin "C") (pinfunction "C_C") (pintype "passive"))
    )
    (net (code "17") (name "C15") (class "Default")
      (node (ref "ATMEGA32U4-AU") (pin "25") (pinfunction "PD4_25") (pintype "bidirectional"))
      (node (ref "D15") (pin "C") (pinfunction "C_C") (pintype "passive"))
      (node (ref "D32") (pin "C") (pinfunction "C_C") (pintype "passive"))
      (node (ref "D49") (pin "C") (pinfunction "C_C") (pintype "passive"))
      (node (ref "D65") (pin "C") (pinfunction "C_C") (pintype "passive"))
    )
    (net (code "18") (name "C16") (class "Default")
      (node (ref "ATMEGA32U4-AU") (pin "22") (pinfunction "PD5_22") (pintype "bidirectional"))
      (node (ref "D16") (pin "C") (pinfunction "C_C") (pintype "passive"))
      (node (ref "D33") (pin "C") (pinfunction "C_C") (pintype "passive"))
      (node (ref "D50") (pin "C") (pinfunction "C_C") (pintype "passive"))
      (node (ref "D66") (pin "C") (pinfunction "C_C") (pintype "passive"))
    )
    (net (code "19") (name "C17") (class "Default")
      (node (ref "ATMEGA32U4-AU") (pin "27") (pinfunction "PD7_27") (pintype "bidirectional"))
      (node (ref "D17") (pin "C") (pinfunction "C_C") (pintype "passive"))
      (node (ref "D34") (pin "C") (pinfunction "C_C") (pintype "passive"))
    )
    (net (code "20") (name "Net-(ATMEGA32U4-AU-D+)") (class "Default")
      (node (ref "ATMEGA32U4-AU") (pin "4") (pinfunction "D+_4") (pintype "passive"))
      (node (ref "R2") (pin "2") (pinfunction "2_2") (pintype "passive"))
    )
    (net (code "21") (name "Net-(ATMEGA32U4-AU-D-)") (class "Default")
      (node (ref "ATMEGA32U4-AU") (pin "3") (pinfunction "D-_3") (pintype "passive"))
      (node (ref "R1") (pin "2") (pinfunction "2_2") (pintype "passive"))
    )
    (net (code "22") (name "Net-(ATMEGA32U4-AU-UCAP)") (class "Default")
      (node (ref "ATMEGA32U4-AU") (pin "6") (pinfunction "UCAP_6") (pintype "power_in"))
      (node (ref "C4") (pin "1") (pinfunction "1_1") (pintype "passive"))
    )
    (net (code "23") (name "Net-(ATMEGA32U4-AU-XTAL1)") (class "Default")
      (node (ref "ATMEGA32U4-AU") (pin "17") (pinfunction "XTAL1_17") (pintype "input"))
      (node (ref "C2") (pin "1") (pinfunction "1_1") (pintype "passive"))
      (node (ref "Y1") (pin "1") (pinfunction "1_1") (pintype "passive"))
    )
    (net (code "24") (name "Net-(ATMEGA32U4-AU-XTAL2)") (class "Default")
      (node (ref "ATMEGA32U4-AU") (pin "16") (pinfunction "XTAL2_16") (pintype "output"))
      (node (ref "C3") (pin "1") (pinfunction "1_1") (pintype "passive"))
      (node (ref "Y1") (pin "3") (pinfunction "2_3") (pintype "passive"))
    )
    (net (code "25") (name "Net-(ATMEGA32U4-AU-~{RESET})") (class "Default")
      (node (ref "ATMEGA32U4-AU") (pin "13") (pinfunction "~{RESET}_13") (pintype "input"))
      (node (ref "ISP") (pin "5") (pinfunction "5_5") (pintype "bidirectional"))
      (node (ref "S80") (pin "3") (pinfunction "2_3") (pintype "passive"))
    )
    (net (code "26") (name "Net-(S1-2)") (class "Default")
      (node (ref "D1") (pin "A") (pinfunction "A_A") (pintype "passive"))
      (node (ref "S1") (pin "S2") (pinfunction "2_S2") (pintype "passive"))
    )
    (net (code "27") (name "Net-(S2-2)") (class "Default")
      (node (ref "D2") (pin "A") (pinfunction "A_A") (pintype "passive"))
      (node (ref "S2") (pin "S2") (pinfunction "2_S2") (pintype "passive"))
    )
    (net (code "28") (name "Net-(S3-2)") (class "Default")
      (node (ref "D3") (pin "A") (pinfunction "A_A") (pintype "passive"))
      (node (ref "S3") (pin "S2") (pinfunction "2_S2") (pintype "passive"))
    )
    (net (code "29") (name "Net-(S4-2)") (class "Default")
      (node (ref "D4") (pin "A") (pinfunction "A_A") (pintype "passive"))
      (node (ref "S4") (pin "S2") (pinfunction "2_S2") (pintype "passive"))
    )
    (net (code "30") (name "Net-(S5-2)") (class "Default")
      (node (ref "D5") (pin "A") (pinfunction "A_A") (pintype "passive"))
      (node (ref "S5") (pin "S2") (pinfunction "2_S2") (pintype "passive"))
    )
    (net (code "31") (name "Net-(S6-2)") (class "Default")
      (node (ref "D6") (pin "A") (pinfunction "A_A") (pintype "passive"))
      (node (ref "S6") (pin "S2") (pinfunction "2_S2") (pintype "passive"))
    )
    (net (code "32") (name "Net-(S7-2)") (class "Default")
      (node (ref "D7") (pin "A") (pinfunction "A_A") (pintype "passive"))
      (node (ref "S7") (pin "S2") (pinfunction "2_S2") (pintype "passive"))
    )
    (net (code "33") (name "Net-(S8-2)") (class "Default")
      (node (ref "D8") (pin "A") (pinfunction "A_A") (pintype "passive"))
      (node (ref "S8") (pin "S2") (pinfunction "2_S2") (pintype "passive"))
    )
    (net (code "34") (name "Net-(S9-2)") (class "Default")
      (node (ref "D9") (pin "A") (pinfunction "A_A") (pintype "passive"))
      (node (ref "S9") (pin "S2") (pinfunction "2_S2") (pintype "passive"))
    )
    (net (code "35") (name "Net-(S10-2)") (class "Default")
      (node (ref "D10") (pin "A") (pinfunction "A_A") (pintype "passive"))
      (node (ref "S10") (pin "S2") (pinfunction "2_S2") (pintype "passive"))
    )
    (net (code "36") (name "Net-(S11-2)") (class "Default")
      (node (ref "D11") (pin "A") (pinfunction "A_A") (pintype "passive"))
      (node (ref "S11") (pin "S2") (pinfunction "2_S2") (pintype "passive"))
    )
    (net (code "37") (name "Net-(S12-2)") (class "Default")
      (node (ref "D12") (pin "A") (pinfunction "A_A") (pintype "passive"))
      (node (ref "S12") (pin "S2") (pinfunction "2_S2") (pintype "passive"))
    )
    (net (code "38") (name "Net-(S13-2)") (class "Default")
      (node (ref "D13") (pin "A") (pinfunction "A_A") (pintype "passive"))
      (node (ref "S13") (pin "S2") (pinfunction "2_S2") (pintype "passive"))
    )
    (net (code "39") (name "Net-(S14-2)") (class "Default")
      (node (ref "D14") (pin "A") (pinfunction "A_A") (pintype "passive"))
      (node (ref "S14") (pin "S2") (pinfunction "2_S2") (pintype "passive"))
    )
    (net (code "40") (name "Net-(S15-2)") (class "Default")
      (node (ref "D15") (pin "A") (pinfunction "A_A") (pintype "passive"))
      (node (ref "S15") (pin "S2") (pinfunction "2_S2") (pintype "passive"))
    )
    (net (code "41") (name "Net-(S16-2)") (class "Default")
      (node (ref "D16") (pin "A") (pinfunction "A_A") (pintype "passive"))
      (node (ref "S16") (pin "S2") (pinfunction "2_S2") (pintype "passive"))
    )
    (net (code "42") (name "Net-(S17-2)") (class "Default")
      (node (ref "D17") (pin "A") (pinfunction "A_A") (pintype "passive"))
      (node (ref "S17") (pin "S2") (pinfunction "2_S2") (pintype "passive"))
    )
    (net (code "43") (name "Net-(S18-2)") (class "Default")
      (node (ref "D18") (pin "A") (pinfunction "A_A") (pintype "passive"))
      (node (ref "S18") (pin "S2") (pinfunction "2_S2") (pintype "passive"))
    )
    (net (code "44") (name "Net-(S19-2)") (class "Default")
      (node (ref "D19") (pin "A") (pinfunction "A_A") (pintype "passive"))
      (node (ref "S19") (pin "S2") (pinfunction "2_S2") (pintype "passive"))
    )
    (net (code "45") (name "Net-(S20-2)") (class "Default")
      (node (ref "D20") (pin "A") (pinfunction "A_A") (pintype "passive"))
      (node (ref "S20") (pin "S2") (pinfunction "2_S2") (pintype "passive"))
    )
    (net (code "46") (name "Net-(S21-2)") (class "Default")
      (node (ref "D21") (pin "A") (pinfunction "A_A") (pintype "passive"))
      (node (ref "S21") (pin "S2") (pinfunction "2_S2") (pintype "passive"))
    )
    (net (code "47") (name "Net-(S22-2)") (class "Default")
      (node (ref "D22") (pin "A") (pinfunction "A_A") (pintype "passive"))
      (node (ref "S22") (pin "S2") (pinfunction "2_S2") (pintype "passive"))
    )
    (net (code "48") (name "Net-(S23-2)") (class "Default")
      (node (ref "D23") (pin "A") (pinfunction "A_A") (pintype "passive"))
      (node (ref "S23") (pin "S2") (pinfunction "2_S2") (pintype "passive"))
    )
    (net (code "49") (name "Net-(S24-2)") (class "Default")
      (node (ref "D24") (pin "A") (pinfunction "A_A") (pintype "passive"))
      (node (ref "S24") (pin "S2") (pinfunction "2_S2") (pintype "passive"))
    )
    (net (code "50") (name "Net-(S25-2)") (class "Default")
      (node (ref "D25") (pin "A") (pinfunction "A_A") (pintype "passive"))
      (node (ref "S25") (pin "S2") (pinfunction "2_S2") (pintype "passive"))
    )
    (net (code "51") (name "Net-(S26-2)") (class "Default")
      (node (ref "D26") (pin "A") (pinfunction "A_A") (pintype "passive"))
      (node (ref "S26") (pin "S2") (pinfunction "2_S2") (pintype "passive"))
    )
    (net (code "52") (name "Net-(S27-2)") (class "Default")
      (node (ref "D27") (pin "A") (pinfunction "A_A") (pintype "passive"))
      (node (ref "S27") (pin "S2") (pinfunction "2_S2") (pintype "passive"))
    )
    (net (code "53") (name "Net-(S28-2)") (class "Default")
      (node (ref "D28") (pin "A") (pinfunction "A_A") (pintype "passive"))
      (node (ref "S28") (pin "S2") (pinfunction "2_S2") (pintype "passive"))
    )
    (net (code "54") (name "Net-(S29-2)") (class "Default")
      (node (ref "D29") (pin "A") (pinfunction "A_A") (pintype "passive"))
      (node (ref "S29") (pin "S2") (pinfunction "2_S2") (pintype "passive"))
    )
    (net (code "55") (name "Net-(S30-2)") (class "Default")
      (node (ref "D30") (pin "A") (pinfunction "A_A") (pintype "passive"))
      (node (ref "S30") (pin "S2") (pinfunction "2_S2") (pintype "passive"))
    )
    (net (code "56") (name "Net-(S31-2)") (class "Default")
      (node (ref "D31") (pin "A") (pinfunction "A_A") (pintype "passive"))
      (node (ref "S31") (pin "S2") (pinfunction "2_S2") (pintype "passive"))
    )
    (net (code "57") (name "Net-(S32-2)") (class "Default")
      (node (ref "D32") (pin "A") (pinfunction "A_A") (pintype "passive"))
      (node (ref "S32") (pin "S2") (pinfunction "2_S2") (pintype "passive"))
    )
    (net (code "58") (name "Net-(S33-2)") (class "Default")
      (node (ref "D33") (pin "A") (pinfunction "A_A") (pintype "passive"))
      (node (ref "S33") (pin "S2") (pinfunction "2_S2") (pintype "passive"))
    )
    (net (code "59") (name "Net-(S34-2)") (class "Default")
      (node (ref "D34") (pin "A") (pinfunction "A_A") (pintype "passive"))
      (node (ref "S34") (pin "S2") (pinfunction "2_S2") (pintype "passive"))
    )
    (net (code "60") (name "Net-(S35-2)") (class "Default")
      (node (ref "D35") (pin "A") (pinfunction "A_A") (pintype "passive"))
      (node (ref "S35") (pin "S2") (pinfunction "2_S2") (pintype "passive"))
    )
    (net (code "61") (name "Net-(S36-2)") (class "Default")
      (node (ref "D36") (pin "A") (pinfunction "A_A") (pintype "passive"))
      (node (ref "S36") (pin "S2") (pinfunction "2_S2") (pintype "passive"))
    )
    (net (code "62") (name "Net-(S37-2)") (class "Default")
      (node (ref "D37") (pin "A") (pinfunction "A_A") (pintype "passive"))
      (node (ref "S37") (pin "S2") (pinfunction "2_S2") (pintype "passive"))
    )
    (net (code "63") (name "Net-(S38-2)") (class "Default")
      (node (ref "D38") (pin "A") (pinfunction "A_A") (pintype "passive"))
      (node (ref "S38") (pin "S2") (pinfunction "2_S2") (pintype "passive"))
    )
    (net (code "64") (name "Net-(S39-2)") (class "Default")
      (node (ref "D39") (pin "A") (pinfunction "A_A") (pintype "passive"))
      (node (ref "S39") (pin "S2") (pinfunction "2_S2") (pintype "passive"))
    )
    (net (code "65") (name "Net-(S40-2)") (class "Default")
      (node (ref "D40") (pin "A") (pinfunction "A_A") (pintype "passive"))
      (node (ref "S40") (pin "S2") (pinfunction "2_S2") (pintype "passive"))
    )
    (net (code "66") (name "Net-(S41-2)") (class "Default")
      (node (ref "D41") (pin "A") (pinfunction "A_A") (pintype "passive"))
      (node (ref "S41") (pin "S2") (pinfunction "2_S2") (pintype "passive"))
    )
    (net (code "67") (name "Net-(S42-2)") (class "Default")
      (node (ref "D42") (pin "A") (pinfunction "A_A") (pintype "passive"))
      (node (ref "S42") (pin "S2") (pinfunction "2_S2") (pintype "passive"))
    )
    (net (code "68") (name "Net-(S43-2)") (class "Default")
      (node (ref "D43") (pin "A") (pinfunction "A_A") (pintype "passive"))
      (node (ref "S43") (pin "S2") (pinfunction "2_S2") (pintype "passive"))
    )
    (net (code "69") (name "Net-(S44-2)") (class "Default")
      (node (ref "D44") (pin "A") (pinfunction "A_A") (pintype "passive"))
      (node (ref "S44") (pin "S2") (pinfunction "2_S2") (pintype "passive"))
    )
    (net (code "70") (name "Net-(S45-2)") (class "Default")
      (node (ref "D45") (pin "A") (pinfunction "A_A") (pintype "passive"))
      (node (ref "S45") (pin "S2") (pinfunction "2_S2") (pintype "passive"))
    )
    (net (code "71") (name "Net-(S46-2)") (class "Default")
      (node (ref "D46") (pin "A") (pinfunction "A_A") (pintype "passive"))
      (node (ref "S46") (pin "S2") (pinfunction "2_S2") (pintype "passive"))
    )
    (net (code "72") (name "Net-(S47-2)") (class "Default")
      (node (ref "D47") (pin "A") (pinfunction "A_A") (pintype "passive"))
      (node (ref "S47") (pin "S2") (pinfunction "2_S2") (pintype "passive"))
    )
    (net (code "73") (name "Net-(S48-2)") (class "Default")
      (node (ref "D48") (pin "A") (pinfunction "A_A") (pintype "passive"))
      (node (ref "S48") (pin "S2") (pinfunction "2_S2") (pintype "passive"))
    )
    (net (code "74") (name "Net-(S49-2)") (class "Default")
      (node (ref "D49") (pin "A") (pinfunction "A_A") (pintype "passive"))
      (node (ref "S49") (pin "S2") (pinfunction "2_S2") (pintype "passive"))
    )
    (net (code "75") (name "Net-(S50-2)") (class "Default")
      (node (ref "D50") (pin "A") (pinfunction "A_A") (pintype "passive"))
      (node (ref "S50") (pin "S2") (pinfunction "2_S2") (pintype "passive"))
    )
    (net (code "76") (name "Net-(S51-2)") (class "Default")
      (node (ref "D51") (pin "A") (pinfunction "A_A") (pintype "passive"))
      (node (ref "S51") (pin "S2") (pinfunction "2_S2") (pintype "passive"))
    )
    (net (code "77") (name "Net-(S52-2)") (class "Default")
      (node (ref "D52") (pin "A") (pinfunction "A_A") (pintype "passive"))
      (node (ref "S52") (pin "S2") (pinfunction "2_S2") (pintype "passive"))
    )
    (net (code "78") (name "Net-(S53-2)") (class "Default")
      (node (ref "D53") (pin "A") (pinfunction "A_A") (pintype "passive"))
      (node (ref "S53") (pin "S2") (pinfunction "2_S2") (pintype "passive"))
    )
    (net (code "79") (name "Net-(S54-2)") (class "Default")
      (node (ref "D54") (pin "A") (pinfunction "A_A") (pintype "passive"))
      (node (ref "S54") (pin "S2") (pinfunction "2_S2") (pintype "passive"))
    )
    (net (code "80") (name "Net-(S55-2)") (class "Default")
      (node (ref "D55") (pin "A") (pinfunction "A_A") (pintype "passive"))
      (node (ref "S55") (pin "S2") (pinfunction "2_S2") (pintype "passive"))
    )
    (net (code "81") (name "Net-(S56-2)") (class "Default")
      (node (ref "D56") (pin "A") (pinfunction "A_A") (pintype "passive"))
      (node (ref "S56") (pin "S2") (pinfunction "2_S2") (pintype "passive"))
    )
    (net (code "82") (name "Net-(S57-2)") (class "Default")
      (node (ref "D57") (pin "A") (pinfunction "A_A") (pintype "passive"))
      (node (ref "S57") (pin "S2") (pinfunction "2_S2") (pintype "passive"))
    )
    (net (code "83") (name "Net-(S58-2)") (class "Default")
      (node (ref "D58") (pin "A") (pinfunction "A_A") (pintype "passive"))
      (node (ref "S58") (pin "S2") (pinfunction "2_S2") (pintype "passive"))
    )
    (net (code "84") (name "Net-(S59-2)") (class "Default")
      (node (ref "D59") (pin "A") (pinfunction "A_A") (pintype "passive"))
      (node (ref "S59") (pin "S2") (pinfunction "2_S2") (pintype "passive"))
    )
    (net (code "85") (name "Net-(S60-2)") (class "Default")
      (node (ref "D60") (pin "A") (pinfunction "A_A") (pintype "passive"))
      (node (ref "S60") (pin "S2") (pinfunction "2_S2") (pintype "passive"))
    )
    (net (code "86") (name "Net-(S61-2)") (class "Default")
      (node (ref "D61") (pin "A") (pinfunction "A_A") (pintype "passive"))
      (node (ref "S61") (pin "S2") (pinfunction "2_S2") (pintype "passive"))
    )
    (net (code "87") (name "Net-(S62-2)") (class "Default")
      (node (ref "D62") (pin "A") (pinfunction "A_A") (pintype "passive"))
      (node (ref "S62") (pin "S2") (pinfunction "2_S2") (pintype "passive"))
    )
    (net (code "88") (name "Net-(S63-2)") (class "Default")
      (node (ref "D63") (pin "A") (pinfunction "A_A") (pintype "passive"))
      (node (ref "S63") (pin "S2") (pinfunction "2_S2") (pintype "passive"))
    )
    (net (code "89") (name "Net-(S64-2)") (class "Default")
      (node (ref "D64") (pin "A") (pinfunction "A_A") (pintype "passive"))
      (node (ref "S64") (pin "S2") (pinfunction "2_S2") (pintype "passive"))
    )
    (net (code "90") (name "Net-(S65-2)") (class "Default")
      (node (ref "D65") (pin "A") (pinfunction "A_A") (pintype "passive"))
      (node (ref "S65") (pin "S2") (pinfunction "2_S2") (pintype "passive"))
    )
    (net (code "91") (name "Net-(S66-2)") (class "Default")
      (node (ref "D66") (pin "A") (pinfunction "A_A") (pintype "passive"))
      (node (ref "S66") (pin "S2") (pinfunction "2_S2") (pintype "passive"))
    )
    (net (code "92") (name "Net-(S67-2)") (class "Default")
      (node (ref "D67") (pin "A") (pinfunction "A_A") (pintype "passive"))
      (node (ref "S67") (pin "S2") (pinfunction "2_S2") (pintype "passive"))
    )
    (net (code "93") (name "Net-(S68-2)") (class "Default")
      (node (ref "D68") (pin "A") (pinfunction "A_A") (pintype "passive"))
      (node (ref "S68") (pin "S2") (pinfunction "2_S2") (pintype "passive"))
    )
    (net (code "94") (name "Net-(S69-2)") (class "Default")
      (node (ref "D69") (pin "A") (pinfunction "A_A") (pintype "passive"))
      (node (ref "S69") (pin "S2") (pinfunction "2_S2") (pintype "passive"))
    )
    (net (code "95") (name "Net-(S70-2)") (class "Default")
      (node (ref "D70") (pin "A") (pinfunction "A_A") (pintype "passive"))
      (node (ref "S70") (pin "S2") (pinfunction "2_S2") (pintype "passive"))
    )
    (net (code "96") (name "Net-(S71-2)") (class "Default")
      (node (ref "D71") (pin "A") (pinfunction "A_A") (pintype "passive"))
      (node (ref "S71") (pin "S2") (pinfunction "2_S2") (pintype "passive"))
    )
    (net (code "97") (name "Net-(S72-2)") (class "Default")
      (node (ref "D72") (pin "A") (pinfunction "A_A") (pintype "passive"))
      (node (ref "S72") (pin "S2") (pinfunction "2_S2") (pintype "passive"))
    )
    (net (code "98") (name "Net-(S73-2)") (class "Default")
      (node (ref "D73") (pin "A") (pinfunction "A_A") (pintype "passive"))
      (node (ref "S73") (pin "S2") (pinfunction "2_S2") (pintype "passive"))
    )
    (net (code "99") (name "Net-(S74-2)") (class "Default")
      (node (ref "D74") (pin "A") (pinfunction "A_A") (pintype "passive"))
      (node (ref "S74") (pin "S2") (pinfunction "2_S2") (pintype "passive"))
    )
    (net (code "100") (name "Net-(S75-2)") (class "Default")
      (node (ref "D75") (pin "A") (pinfunction "A_A") (pintype "passive"))
      (node (ref "S75") (pin "S2") (pinfunction "2_S2") (pintype "passive"))
    )
    (net (code "101") (name "Net-(S76-2)") (class "Default")
      (node (ref "D76") (pin "A") (pinfunction "A_A") (pintype "passive"))
      (node (ref "S76") (pin "S2") (pinfunction "2_S2") (pintype "passive"))
    )
    (net (code "102") (name "Net-(S77-2)") (class "Default")
      (node (ref "D77") (pin "A") (pinfunction "A_A") (pintype "passive"))
      (node (ref "S77") (pin "S2") (pinfunction "2_S2") (pintype "passive"))
    )
    (net (code "103") (name "Net-(S78-2)") (class "Default")
      (node (ref "D78") (pin "A") (pinfunction "A_A") (pintype "passive"))
      (node (ref "S78") (pin "S2") (pinfunction "2_S2") (pintype "passive"))
    )
    (net (code "104") (name "Net-(S79-2)") (class "Default")
      (node (ref "D79") (pin "A") (pinfunction "A_A") (pintype "passive"))
      (node (ref "S79") (pin "S2") (pinfunction "2_S2") (pintype "passive"))
    )
    (net (code "105") (name "Net-(U$1-A5CC1)") (class "Default")
      (node (ref "R3") (pin "1") (pinfunction "1_1") (pintype "passive"))
      (node (ref "U$1") (pin "A5") (pinfunction "A5CC1_A5") (pintype "bidirectional"))
    )
    (net (code "106") (name "Net-(U$1-A6DP1)") (class "Default")
      (node (ref "R2") (pin "1") (pinfunction "1_1") (pintype "passive"))
      (node (ref "U$1") (pin "A6") (pinfunction "A6DP1_A6") (pintype "bidirectional"))
      (node (ref "U$1") (pin "B6") (pinfunction "B6DP2_B6") (pintype "bidirectional"))
    )
    (net (code "107") (name "Net-(U$1-A7DN1)") (class "Default")
      (node (ref "R1") (pin "1") (pinfunction "1_1") (pintype "passive"))
      (node (ref "U$1") (pin "A7") (pinfunction "A7DN1_A7") (pintype "bidirectional"))
      (node (ref "U$1") (pin "B7") (pinfunction "B7DN2_B7") (pintype "bidirectional"))
    )
    (net (code "108") (name "Net-(U$1-B5CC2)") (class "Default")
      (node (ref "R4") (pin "1") (pinfunction "1_1") (pintype "passive"))
      (node (ref "U$1") (pin "B5") (pinfunction "B5CC2_B5") (pintype "bidirectional"))
    )
    (net (code "109") (name "R1") (class "Default")
      (node (ref "ATMEGA32U4-AU") (pin "41") (pinfunction "PF0_41") (pintype "bidirectional"))
      (node (ref "S1") (pin "S1") (pinfunction "1_S1") (pintype "passive"))
      (node (ref "S10") (pin "S1") (pinfunction "1_S1") (pintype "passive"))
      (node (ref "S11") (pin "S1") (pinfunction "1_S1") (pintype "passive"))
      (node (ref "S12") (pin "S1") (pinfunction "1_S1") (pintype "passive"))
      (node (ref "S13") (pin "S1") (pinfunction "1_S1") (pintype "passive"))
      (node (ref "S14") (pin "S1") (pinfunction "1_S1") (pintype "passive"))
      (node (ref "S15") (pin "S1") (pinfunction "1_S1") (pintype "passive"))
      (node (ref "S16") (pin "S1") (pinfunction "1_S1") (pintype "passive"))
      (node (ref "S17") (pin "S1") (pinfunction "1_S1") (pintype "passive"))
      (node (ref "S2") (pin "S1") (pinfunction "1_S1") (pintype "passive"))
      (node (ref "S3") (pin "S1") (pinfunction "1_S1") (pintype "passive"))
      (node (ref "S4") (pin "S1") (pinfunction "1_S1") (pintype "passive"))
      (node (ref "S5") (pin "S1") (pinfunction "1_S1") (pintype "passive"))
      (node (ref "S6") (pin "S1") (pinfunction "1_S1") (pintype "passive"))
      (node (ref "S7") (pin "S1") (pinfunction "1_S1") (pintype "passive"))
      (node (ref "S8") (pin "S1") (pinfunction "1_S1") (pintype "passive"))
      (node (ref "S9") (pin "S1") (pinfunction "1_S1") (pintype "passive"))
    )
    (net (code "110") (name "R2") (class "Default")
      (node (ref "ATMEGA32U4-AU") (pin "40") (pinfunction "PF1_40") (pintype "bidirectional"))
      (node (ref "S18") (pin "S1") (pinfunction "1_S1") (pintype "passive"))
      (node (ref "S19") (pin "S1") (pinfunction "1_S1") (pintype "passive"))
      (node (ref "S20") (pin "S1") (pinfunction "1_S1") (pintype "passive"))
      (node (ref "S21") (pin "S1") (pinfunction "1_S1") (pintype "passive"))
      (node (ref "S22") (pin "S1") (pinfunction "1_S1") (pintype "passive"))
      (node (ref "S23") (pin "S1") (pinfunction "1_S1") (pintype "passive"))
      (node (ref "S24") (pin "S1") (pinfunction "1_S1") (pintype "passive"))
      (node (ref "S25") (pin "S1") (pinfunction "1_S1") (pintype "passive"))
      (node (ref "S26") (pin "S1") (pinfunction "1_S1") (pintype "passive"))
      (node (ref "S27") (pin "S1") (pinfunction "1_S1") (pintype "passive"))
      (node (ref "S28") (pin "S1") (pinfunction "1_S1") (pintype "passive"))
      (node (ref "S29") (pin "S1") (pinfunction "1_S1") (pintype "passive"))
      (node (ref "S30") (pin "S1") (pinfunction "1_S1") (pintype "passive"))
      (node (ref "S31") (pin "S1") (pinfunction "1_S1") (pintype "passive"))
      (node (ref "S32") (pin "S1") (pinfunction "1_S1") (pintype "passive"))
      (node (ref "S33") (pin "S1") (pinfunction "1_S1") (pintype "passive"))
      (node (ref "S34") (pin "S1") (pinfunction "1_S1") (pintype "passive"))
    )
    (net (code "111") (name "R3") (class "Default")
      (node (ref "ATMEGA32U4-AU") (pin "39") (pinfunction "PF4_39") (pintype "bidirectional"))
      (node (ref "S35") (pin "S1") (pinfunction "1_S1") (pintype "passive"))
      (node (ref "S36") (pin "S1") (pinfunction "1_S1") (pintype "passive"))
      (node (ref "S37") (pin "S1") (pinfunction "1_S1") (pintype "passive"))
      (node (ref "S38") (pin "S1") (pinfunction "1_S1") (pintype "passive"))
      (node (ref "S39") (pin "S1") (pinfunction "1_S1") (pintype "passive"))
      (node (ref "S40") (pin "S1") (pinfunction "1_S1") (pintype "passive"))
      (node (ref "S41") (pin "S1") (pinfunction "1_S1") (pintype "passive"))
      (node (ref "S42") (pin "S1") (pinfunction "1_S1") (pintype "passive"))
      (node (ref "S43") (pin "S1") (pinfunction "1_S1") (pintype "passive"))
      (node (ref "S44") (pin "S1") (pinfunction "1_S1") (pintype "passive"))
      (node (ref "S45") (pin "S1") (pinfunction "1_S1") (pintype "passive"))
      (node (ref "S46") (pin "S1") (pinfunction "1_S1") (pintype "passive"))
      (node (ref "S47") (pin "S1") (pinfunction "1_S1") (pintype "passive"))
      (node (ref "S48") (pin "S1") (pinfunction "1_S1") (pintype "passive"))
      (node (ref "S49") (pin "S1") (pinfunction "1_S1") (pintype "passive"))
      (node (ref "S50") (pin "S1") (pinfunction "1_S1") (pintype "passive"))
    )
    (net (code "112") (name "R4") (class "Default")
      (node (ref "ATMEGA32U4-AU") (pin "38") (pinfunction "PF5_38") (pintype "bidirectional"))
      (node (ref "S51") (pin "S1") (pinfunction "1_S1") (pintype "passive"))
      (node (ref "S52") (pin "S1") (pinfunction "1_S1") (pintype "passive"))
      (node (ref "S53") (pin "S1") (pinfunction "1_S1") (pintype "passive"))
      (node (ref "S54") (pin "S1") (pinfunction "1_S1") (pintype "passive"))
      (node (ref "S55") (pin "S1") (pinfunction "1_S1") (pintype "passive"))
      (node (ref "S56") (pin "S1") (pinfunction "1_S1") (pintype "passive"))
      (node (ref "S57") (pin "S1") (pinfunction "1_S1") (pintype "passive"))
      (node (ref "S58") (pin "S1") (pinfunction "1_S1") (pintype "passive"))
      (node (ref "S59") (pin "S1") (pinfunction "1_S1") (pintype "passive"))
      (node (ref "S60") (pin "S1") (pinfunction "1_S1") (pintype "passive"))
      (node (ref "S61") (pin "S1") (pinfunction "1_S1") (pintype "passive"))
      (node (ref "S62") (pin "S1") (pinfunction "1_S1") (pintype "passive"))
      (node (ref "S63") (pin "S1") (pinfunction "1_S1") (pintype "passive"))
      (node (ref "S64") (pin "S1") (pinfunction "1_S1") (pintype "passive"))
      (node (ref "S65") (pin "S1") (pinfunction "1_S1") (pintype "passive"))
      (node (ref "S66") (pin "S1") (pinfunction "1_S1") (pintype "passive"))
    )
    (net (code "113") (name "R5") (class "Default")
      (node (ref "ATMEGA32U4-AU") (pin "37") (pinfunction "PF6_37") (pintype "bidirectional"))
      (node (ref "S67") (pin "S1") (pinfunction "1_S1") (pintype "passive"))
      (node (ref "S68") (pin "S1") (pinfunction "1_S1") (pintype "passive"))
      (node (ref "S69") (pin "S1") (pinfunction "1_S1") (pintype "passive"))
      (node (ref "S70") (pin "S1") (pinfunction "1_S1") (pintype "passive"))
      (node (ref "S71") (pin "S1") (pinfunction "1_S1") (pintype "passive"))
      (node (ref "S72") (pin "S1") (pinfunction "1_S1") (pintype "passive"))
      (node (ref "S73") (pin "S1") (pinfunction "1_S1") (pintype "passive"))
      (node (ref "S74") (pin "S1") (pinfunction "1_S1") (pintype "passive"))
      (node (ref "S75") (pin "S1") (pinfunction "1_S1") (pintype "passive"))
      (node (ref "S76") (pin "S1") (pinfunction "1_S1") (pintype "passive"))
      (node (ref "S77") (pin "S1") (pinfunction "1_S1") (pintype "passive"))
      (node (ref "S78") (pin "S1") (pinfunction "1_S1") (pintype "passive"))
      (node (ref "S79") (pin "S1") (pinfunction "1_S1") (pintype "passive"))
    )
    (net (code "114") (name "unconnected-(ATMEGA32U4-AU-AREF-Pad42)") (class "Default")
      (node (ref "ATMEGA32U4-AU") (pin "42") (pinfunction "AREF_42") (pintype "input"))
    )
    (net (code "115") (name "unconnected-(ATMEGA32U4-AU-PD6-Pad26)") (class "Default")
      (node (ref "ATMEGA32U4-AU") (pin "26") (pinfunction "PD6_26") (pintype "bidirectional"))
    )
    (net (code "116") (name "unconnected-(ATMEGA32U4-AU-PE2-Pad33)") (class "Default")
      (node (ref "ATMEGA32U4-AU") (pin "33") (pinfunction "PE2_33") (pintype "bidirectional"))
    )
    (net (code "117") (name "unconnected-(ATMEGA32U4-AU-PE6-Pad1)") (class "Default")
      (node (ref "ATMEGA32U4-AU") (pin "1") (pinfunction "PE6_1") (pintype "bidirectional"))
    )
    (net (code "118") (name "unconnected-(ATMEGA32U4-AU-PF7-Pad36)") (class "Default")
      (node (ref "ATMEGA32U4-AU") (pin "36") (pinfunction "PF7_36") (pintype "bidirectional"))
    )
    (net (code "119") (name "unconnected-(S1-C-PadK)") (class "Default")
      (node (ref "S1") (pin "K") (pinfunction "C_K") (pintype "passive"))
    )
    (net (code "120") (name "unconnected-(S1-PadA)") (class "Default")
      (node (ref "S1") (pin "A") (pinfunction "A_A") (pintype "passive"))
    )
    (net (code "121") (name "unconnected-(S2-C-PadK)") (class "Default")
      (node (ref "S2") (pin "K") (pinfunction "C_K") (pintype "passive"))
    )
    (net (code "122") (name "unconnected-(S2-PadA)") (class "Default")
      (node (ref "S2") (pin "A") (pinfunction "A_A") (pintype "passive"))
    )
    (net (code "123") (name "unconnected-(S3-C-PadK)") (class "Default")
      (node (ref "S3") (pin "K") (pinfunction "C_K") (pintype "passive"))
    )
    (net (code "124") (name "unconnected-(S3-PadA)") (class "Default")
      (node (ref "S3") (pin "A") (pinfunction "A_A") (pintype "passive"))
    )
    (net (code "125") (name "unconnected-(S4-C-PadK)") (class "Default")
      (node (ref "S4") (pin "K") (pinfunction "C_K") (pintype "passive"))
    )
    (net (code "126") (name "unconnected-(S4-PadA)") (class "Default")
      (node (ref "S4") (pin "A") (pinfunction "A_A") (pintype "passive"))
    )
    (net (code "127") (name "unconnected-(S5-C-PadK)") (class "Default")
      (node (ref "S5") (pin "K") (pinfunction "C_K") (pintype "passive"))
    )
    (net (code "128") (name "unconnected-(S5-PadA)") (class "Default")
      (node (ref "S5") (pin "A") (pinfunction "A_A") (pintype "passive"))
    )
    (net (code "129") (name "unconnected-(S6-C-PadK)") (class "Default")
      (node (ref "S6") (pin "K") (pinfunction "C_K") (pintype "passive"))
    )
    (net (code "130") (name "unconnected-(S6-PadA)") (class "Default")
      (node (ref "S6") (pin "A") (pinfunction "A_A") (pintype "passive"))
    )
    (net (code "131") (name "unconnected-(S7-C-PadK)") (class "Default")
      (node (ref "S7") (pin "K") (pinfunction "C_K") (pintype "passive"))
    )
    (net (code "132") (name "unconnected-(S7-PadA)") (class "Default")
      (node (ref "S7") (pin "A") (pinfunction "A_A") (pintype "passive"))
    )
    (net (code "133") (name "unconnected-(S8-C-PadK)") (class "Default")
      (node (ref "S8") (pin "K") (pinfunction "C_K") (pintype "passive"))
    )
    (net (code "134") (name "unconnected-(S8-PadA)") (class "Default")
      (node (ref "S8") (pin "A") (pinfunction "A_A") (pintype "passive"))
    )
    (net (code "135") (name "unconnected-(S9-C-PadK)") (class "Default")
      (node (ref "S9") (pin "K") (pinfunction "C_K") (pintype "passive"))
    )
    (net (code "136") (name "unconnected-(S9-PadA)") (class "Default")
      (node (ref "S9") (pin "A") (pinfunction "A_A") (pintype "passive"))
    )
    (net (code "137") (name "unconnected-(S10-C-PadK)") (class "Default")
      (node (ref "S10") (pin "K") (pinfunction "C_K") (pintype "passive"))
    )
    (net (code "138") (name "unconnected-(S10-PadA)") (class "Default")
      (node (ref "S10") (pin "A") (pinfunction "A_A") (pintype "passive"))
    )
    (net (code "139") (name "unconnected-(S11-C-PadK)") (class "Default")
      (node (ref "S11") (pin "K") (pinfunction "C_K") (pintype "passive"))
    )
    (net (code "140") (name "unconnected-(S11-PadA)") (class "Default")
      (node (ref "S11") (pin "A") (pinfunction "A_A") (pintype "passive"))
    )
    (net (code "141") (name "unconnected-(S12-C-PadK)") (class "Default")
      (node (ref "S12") (pin "K") (pinfunction "C_K") (pintype "passive"))
    )
    (net (code "142") (name "unconnected-(S12-PadA)") (class "Default")
      (node (ref "S12") (pin "A") (pinfunction "A_A") (pintype "passive"))
    )
    (net (code "143") (name "unconnected-(S13-C-PadK)") (class "Default")
      (node (ref "S13") (pin "K") (pinfunction "C_K") (pintype "passive"))
    )
    (net (code "144") (name "unconnected-(S13-PadA)") (class "Default")
      (node (ref "S13") (pin "A") (pinfunction "A_A") (pintype "passive"))
    )
    (net (code "145") (name "unconnected-(S14-C-PadK)") (class "Default")
      (node (ref "S14") (pin "K") (pinfunction "C_K") (pintype "passive"))
    )
    (net (code "146") (name "unconnected-(S14-PadA)") (class "Default")
      (node (ref "S14") (pin "A") (pinfunction "A_A") (pintype "passive"))
    )
    (net (code "147") (name "unconnected-(S15-C-PadK)") (class "Default")
      (node (ref "S15") (pin "K") (pinfunction "C_K") (pintype "passive"))
    )
    (net (code "148") (name "unconnected-(S15-PadA)") (class "Default")
      (node (ref "S15") (pin "A") (pinfunction "A_A") (pintype "passive"))
    )
    (net (code "149") (name "unconnected-(S16-C-PadK)") (class "Default")
      (node (ref "S16") (pin "K") (pinfunction "C_K") (pintype "passive"))
    )
    (net (code "150") (name "unconnected-(S16-PadA)") (class "Default")
      (node (ref "S16") (pin "A") (pinfunction "A_A") (pintype "passive"))
    )
    (net (code "151") (name "unconnected-(S17-C-PadK)") (class "Default")
      (node (ref "S17") (pin "K") (pinfunction "C_K") (pintype "passive"))
    )
    (net (code "152") (name "unconnected-(S17-PadA)") (class "Default")
      (node (ref "S17") (pin "A") (pinfunction "A_A") (pintype "passive"))
    )
    (net (code "153") (name "unconnected-(S18-C-PadK)") (class "Default")
      (node (ref "S18") (pin "K") (pinfunction "C_K") (pintype "passive"))
    )
    (net (code "154") (name "unconnected-(S18-PadA)") (class "Default")
      (node (ref "S18") (pin "A") (pinfunction "A_A") (pintype "passive"))
    )
    (net (code "155") (name "unconnected-(S19-C-PadK)") (class "Default")
      (node (ref "S19") (pin "K") (pinfunction "C_K") (pintype "passive"))
    )
    (net (code "156") (name "unconnected-(S19-PadA)") (class "Default")
      (node (ref "S19") (pin "A") (pinfunction "A_A") (pintype "passive"))
    )
    (net (code "157") (name "unconnected-(S20-C-PadK)") (class "Default")
      (node (ref "S20") (pin "K") (pinfunction "C_K") (pintype "passive"))
    )
    (net (code "158") (name "unconnected-(S20-PadA)") (class "Default")
      (node (ref "S20") (pin "A") (pinfunction "A_A") (pintype "passive"))
    )
    (net (code "159") (name "unconnected-(S21-C-PadK)") (class "Default")
      (node (ref "S21") (pin "K") (pinfunction "C_K") (pintype "passive"))
    )
    (net (code "160") (name "unconnected-(S21-PadA)") (class "Default")
      (node (ref "S21") (pin "A") (pinfunction "A_A") (pintype "passive"))
    )
    (net (code "161") (name "unconnected-(S22-C-PadK)") (class "Default")
      (node (ref "S22") (pin "K") (pinfunction "C_K") (pintype "passive"))
    )
    (net (code "162") (name "unconnected-(S22-PadA)") (class "Default")
      (node (ref "S22") (pin "A") (pinfunction "A_A") (pintype "passive"))
    )
    (net (code "163") (name "unconnected-(S23-C-PadK)") (class "Default")
      (node (ref "S23") (pin "K") (pinfunction "C_K") (pintype "passive"))
    )
    (net (code "164") (name "unconnected-(S23-PadA)") (class "Default")
      (node (ref "S23") (pin "A") (pinfunction "A_A") (pintype "passive"))
    )
    (net (code "165") (name "unconnected-(S24-C-PadK)") (class "Default")
      (node (ref "S24") (pin "K") (pinfunction "C_K") (pintype "passive"))
    )
    (net (code "166") (name "unconnected-(S24-PadA)") (class "Default")
      (node (ref "S24") (pin "A") (pinfunction "A_A") (pintype "passive"))
    )
    (net (code "167") (name "unconnected-(S25-C-PadK)") (class "Default")
      (node (ref "S25") (pin "K") (pinfunction "C_K") (pintype "passive"))
    )
    (net (code "168") (name "unconnected-(S25-PadA)") (class "Default")
      (node (ref "S25") (pin "A") (pinfunction "A_A") (pintype "passive"))
    )
    (net (code "169") (name "unconnected-(S26-C-PadK)") (class "Default")
      (node (ref "S26") (pin "K") (pinfunction "C_K") (pintype "passive"))
    )
    (net (code "170") (name "unconnected-(S26-PadA)") (class "Default")
      (node (ref "S26") (pin "A") (pinfunction "A_A") (pintype "passive"))
    )
    (net (code "171") (name "unconnected-(S27-C-PadK)") (class "Default")
      (node (ref "S27") (pin "K") (pinfunction "C_K") (pintype "passive"))
    )
    (net (code "172") (name "unconnected-(S27-PadA)") (class "Default")
      (node (ref "S27") (pin "A") (pinfunction "A_A") (pintype "passive"))
    )
    (net (code "173") (name "unconnected-(S28-C-PadK)") (class "Default")
      (node (ref "S28") (pin "K") (pinfunction "C_K") (pintype "passive"))
    )
    (net (code "174") (name "unconnected-(S28-PadA)") (class "Default")
      (node (ref "S28") (pin "A") (pinfunction "A_A") (pintype "passive"))
    )
    (net (code "175") (name "unconnected-(S29-C-PadK)") (class "Default")
      (node (ref "S29") (pin "K") (pinfunction "C_K") (pintype "passive"))
    )
    (net (code "176") (name "unconnected-(S29-PadA)") (class "Default")
      (node (ref "S29") (pin "A") (pinfunction "A_A") (pintype "passive"))
    )
    (net (code "177") (name "unconnected-(S30-C-PadK)") (class "Default")
      (node (ref "S30") (pin "K") (pinfunction "C_K") (pintype "passive"))
    )
    (net (code "178") (name "unconnected-(S30-PadA)") (class "Default")
      (node (ref "S30") (pin "A") (pinfunction "A_A") (pintype "passive"))
    )
    (net (code "179") (name "unconnected-(S31-C-PadK)") (class "Default")
      (node (ref "S31") (pin "K") (pinfunction "C_K") (pintype "passive"))
    )
    (net (code "180") (name "unconnected-(S31-PadA)") (class "Default")
      (node (ref "S31") (pin "A") (pinfunction "A_A") (pintype "passive"))
    )
    (net (code "181") (name "unconnected-(S32-C-PadK)") (class "Default")
      (node (ref "S32") (pin "K") (pinfunction "C_K") (pintype "passive"))
    )
    (net (code "182") (name "unconnected-(S32-PadA)") (class "Default")
      (node (ref "S32") (pin "A") (pinfunction "A_A") (pintype "passive"))
    )
    (net (code "183") (name "unconnected-(S33-C-PadK)") (class "Default")
      (node (ref "S33") (pin "K") (pinfunction "C_K") (pintype "passive"))
    )
    (net (code "184") (name "unconnected-(S33-PadA)") (class "Default")
      (node (ref "S33") (pin "A") (pinfunction "A_A") (pintype "passive"))
    )
    (net (code "185") (name "unconnected-(S34-C-PadK)") (class "Default")
      (node (ref "S34") (pin "K") (pinfunction "C_K") (pintype "passive"))
    )
    (net (code "186") (name "unconnected-(S34-PadA)") (class "Default")
      (node (ref "S34") (pin "A") (pinfunction "A_A") (pintype "passive"))
    )
    (net (code "187") (name "unconnected-(S35-C-PadK)") (class "Default")
      (node (ref "S35") (pin "K") (pinfunction "C_K") (pintype "passive"))
    )
    (net (code "188") (name "unconnected-(S35-PadA)") (class "Default")
      (node (ref "S35") (pin "A") (pinfunction "A_A") (pintype "passive"))
    )
    (net (code "189") (name "unconnected-(S36-C-PadK)") (class "Default")
      (node (ref "S36") (pin "K") (pinfunction "C_K") (pintype "passive"))
    )
    (net (code "190") (name "unconnected-(S36-PadA)") (class "Default")
      (node (ref "S36") (pin "A") (pinfunction "A_A") (pintype "passive"))
    )
    (net (code "191") (name "unconnected-(S37-C-PadK)") (class "Default")
      (node (ref "S37") (pin "K") (pinfunction "C_K") (pintype "passive"))
    )
    (net (code "192") (name "unconnected-(S37-PadA)") (class "Default")
      (node (ref "S37") (pin "A") (pinfunction "A_A") (pintype "passive"))
    )
    (net (code "193") (name "unconnected-(S38-C-PadK)") (class "Default")
      (node (ref "S38") (pin "K") (pinfunction "C_K") (pintype "passive"))
    )
    (net (code "194") (name "unconnected-(S38-PadA)") (class "Default")
      (node (ref "S38") (pin "A") (pinfunction "A_A") (pintype "passive"))
    )
    (net (code "195") (name "unconnected-(S39-C-PadK)") (class "Default")
      (node (ref "S39") (pin "K") (pinfunction "C_K") (pintype "passive"))
    )
    (net (code "196") (name "unconnected-(S39-PadA)") (class "Default")
      (node (ref "S39") (pin "A") (pinfunction "A_A") (pintype "passive"))
    )
    (net (code "197") (name "unconnected-(S40-C-PadK)") (class "Default")
      (node (ref "S40") (pin "K") (pinfunction "C_K") (pintype "passive"))
    )
    (net (code "198") (name "unconnected-(S40-PadA)") (class "Default")
      (node (ref "S40") (pin "A") (pinfunction "A_A") (pintype "passive"))
    )
    (net (code "199") (name "unconnected-(S41-C-PadK)") (class "Default")
      (node (ref "S41") (pin "K") (pinfunction "C_K") (pintype "passive"))
    )
    (net (code "200") (name "unconnected-(S41-PadA)") (class "Default")
      (node (ref "S41") (pin "A") (pinfunction "A_A") (pintype "passive"))
    )
    (net (code "201") (name "unconnected-(S42-C-PadK)") (class "Default")
      (node (ref "S42") (pin "K") (pinfunction "C_K") (pintype "passive"))
    )
    (net (code "202") (name "unconnected-(S42-PadA)") (class "Default")
      (node (ref "S42") (pin "A") (pinfunction "A_A") (pintype "passive"))
    )
    (net (code "203") (name "unconnected-(S43-C-PadK)") (class "Default")
      (node (ref "S43") (pin "K") (pinfunction "C_K") (pintype "passive"))
    )
    (net (code "204") (name "unconnected-(S43-PadA)") (class "Default")
      (node (ref "S43") (pin "A") (pinfunction "A_A") (pintype "passive"))
    )
    (net (code "205") (name "unconnected-(S44-C-PadK)") (class "Default")
      (node (ref "S44") (pin "K") (pinfunction "C_K") (pintype "passive"))
    )
    (net (code "206") (name "unconnected-(S44-PadA)") (class "Default")
      (node (ref "S44") (pin "A") (pinfunction "A_A") (pintype "passive"))
    )
    (net (code "207") (name "unconnected-(S45-C-PadK)") (class "Default")
      (node (ref "S45") (pin "K") (pinfunction "C_K") (pintype "passive"))
    )
    (net (code "208") (name "unconnected-(S45-PadA)") (class "Default")
      (node (ref "S45") (pin "A") (pinfunction "A_A") (pintype "passive"))
    )
    (net (code "209") (name "unconnected-(S46-C-PadK)") (class "Default")
      (node (ref "S46") (pin "K") (pinfunction "C_K") (pintype "passive"))
    )
    (net (code "210") (name "unconnected-(S46-PadA)") (class "Default")
      (node (ref "S46") (pin "A") (pinfunction "A_A") (pintype "passive"))
    )
    (net (code "211") (name "unconnected-(S47-C-PadK)") (class "Default")
      (node (ref "S47") (pin "K") (pinfunction "C_K") (pintype "passive"))
    )
    (net (code "212") (name "unconnected-(S47-PadA)") (class "Default")
      (node (ref "S47") (pin "A") (pinfunction "A_A") (pintype "passive"))
    )
    (net (code "213") (name "unconnected-(S48-C-PadK)") (class "Default")
      (node (ref "S48") (pin "K") (pinfunction "C_K") (pintype "passive"))
    )
    (net (code "214") (name "unconnected-(S48-PadA)") (class "Default")
      (node (ref "S48") (pin "A") (pinfunction "A_A") (pintype "passive"))
    )
    (net (code "215") (name "unconnected-(S49-C-PadK)") (class "Default")
      (node (ref "S49") (pin "K") (pinfunction "C_K") (pintype "passive"))
    )
    (net (code "216") (name "unconnected-(S49-PadA)") (class "Default")
      (node (ref "S49") (pin "A") (pinfunction "A_A") (pintype "passive"))
    )
    (net (code "217") (name "unconnected-(S50-C-PadK)") (class "Default")
      (node (ref "S50") (pin "K") (pinfunction "C_K") (pintype "passive"))
    )
    (net (code "218") (name "unconnected-(S50-PadA)") (class "Default")
      (node (ref "S50") (pin "A") (pinfunction "A_A") (pintype "passive"))
    )
    (net (code "219") (name "unconnected-(S51-C-PadK)") (class "Default")
      (node (ref "S51") (pin "K") (pinfunction "C_K") (pintype "passive"))
    )
    (net (code "220") (name "unconnected-(S51-PadA)") (class "Default")
      (node (ref "S51") (pin "A") (pinfunction "A_A") (pintype "passive"))
    )
    (net (code "221") (name "unconnected-(S52-C-PadK)") (class "Default")
      (node (ref "S52") (pin "K") (pinfunction "C_K") (pintype "passive"))
    )
    (net (code "222") (name "unconnected-(S52-PadA)") (class "Default")
      (node (ref "S52") (pin "A") (pinfunction "A_A") (pintype "passive"))
    )
    (net (code "223") (name "unconnected-(S53-C-PadK)") (class "Default")
      (node (ref "S53") (pin "K") (pinfunction "C_K") (pintype "passive"))
    )
    (net (code "224") (name "unconnected-(S53-PadA)") (class "Default")
      (node (ref "S53") (pin "A") (pinfunction "A_A") (pintype "passive"))
    )
    (net (code "225") (name "unconnected-(S54-C-PadK)") (class "Default")
      (node (ref "S54") (pin "K") (pinfunction "C_K") (pintype "passive"))
    )
    (net (code "226") (name "unconnected-(S54-PadA)") (class "Default")
      (node (ref "S54") (pin "A") (pinfunction "A_A") (pintype "passive"))
    )
    (net (code "227") (name "unconnected-(S55-C-PadK)") (class "Default")
      (node (ref "S55") (pin "K") (pinfunction "C_K") (pintype "passive"))
    )
    (net (code "228") (name "unconnected-(S55-PadA)") (class "Default")
      (node (ref "S55") (pin "A") (pinfunction "A_A") (pintype "passive"))
    )
    (net (code "229") (name "unconnected-(S56-C-PadK)") (class "Default")
      (node (ref "S56") (pin "K") (pinfunction "C_K") (pintype "passive"))
    )
    (net (code "230") (name "unconnected-(S56-PadA)") (class "Default")
      (node (ref "S56") (pin "A") (pinfunction "A_A") (pintype "passive"))
    )
    (net (code "231") (name "unconnected-(S57-C-PadK)") (class "Default")
      (node (ref "S57") (pin "K") (pinfunction "C_K") (pintype "passive"))
    )
    (net (code "232") (name "unconnected-(S57-PadA)") (class "Default")
      (node (ref "S57") (pin "A") (pinfunction "A_A") (pintype "passive"))
    )
    (net (code "233") (name "unconnected-(S58-C-PadK)") (class "Default")
      (node (ref "S58") (pin "K") (pinfunction "C_K") (pintype "passive"))
    )
    (net (code "234") (name "unconnected-(S58-PadA)") (class "Default")
      (node (ref "S58") (pin "A") (pinfunction "A_A") (pintype "passive"))
    )
    (net (code "235") (name "unconnected-(S59-C-PadK)") (class "Default")
      (node (ref "S59") (pin "K") (pinfunction "C_K") (pintype "passive"))
    )
    (net (code "236") (name "unconnected-(S59-PadA)") (class "Default")
      (node (ref "S59") (pin "A") (pinfunction "A_A") (pintype "passive"))
    )
    (net (code "237") (name "unconnected-(S60-C-PadK)") (class "Default")
      (node (ref "S60") (pin "K") (pinfunction "C_K") (pintype "passive"))
    )
    (net (code "238") (name "unconnected-(S60-PadA)") (class "Default")
      (node (ref "S60") (pin "A") (pinfunction "A_A") (pintype "passive"))
    )
    (net (code "239") (name "unconnected-(S61-C-PadK)") (class "Default")
      (node (ref "S61") (pin "K") (pinfunction "C_K") (pintype "passive"))
    )
    (net (code "240") (name "unconnected-(S61-PadA)") (class "Default")
      (node (ref "S61") (pin "A") (pinfunction "A_A") (pintype "passive"))
    )
    (net (code "241") (name "unconnected-(S62-C-PadK)") (class "Default")
      (node (ref "S62") (pin "K") (pinfunction "C_K") (pintype "passive"))
    )
    (net (code "242") (name "unconnected-(S62-PadA)") (class "Default")
      (node (ref "S62") (pin "A") (pinfunction "A_A") (pintype "passive"))
    )
    (net (code "243") (name "unconnected-(S63-C-PadK)") (class "Default")
      (node (ref "S63") (pin "K") (pinfunction "C_K") (pintype "passive"))
    )
    (net (code "244") (name "unconnected-(S63-PadA)") (class "Default")
      (node (ref "S63") (pin "A") (pinfunction "A_A") (pintype "passive"))
    )
    (net (code "245") (name "unconnected-(S64-C-PadK)") (class "Default")
      (node (ref "S64") (pin "K") (pinfunction "C_K") (pintype "passive"))
    )
    (net (code "246") (name "unconnected-(S64-PadA)") (class "Default")
      (node (ref "S64") (pin "A") (pinfunction "A_A") (pintype "passive"))
    )
    (net (code "247") (name "unconnected-(S65-C-PadK)") (class "Default")
      (node (ref "S65") (pin "K") (pinfunction "C_K") (pintype "passive"))
    )
    (net (code "248") (name "unconnected-(S65-PadA)") (class "Default")
      (node (ref "S65") (pin "A") (pinfunction "A_A") (pintype "passive"))
    )
    (net (code "249") (name "unconnected-(S66-C-PadK)") (class "Default")
      (node (ref "S66") (pin "K") (pinfunction "C_K") (pintype "passive"))
    )
    (net (code "250") (name "unconnected-(S66-PadA)") (class "Default")
      (node (ref "S66") (pin "A") (pinfunction "A_A") (pintype "passive"))
    )
    (net (code "251") (name "unconnected-(S67-C-PadK)") (class "Default")
      (node (ref "S67") (pin "K") (pinfunction "C_K") (pintype "passive"))
    )
    (net (code "252") (name "unconnected-(S67-PadA)") (class "Default")
      (node (ref "S67") (pin "A") (pinfunction "A_A") (pintype "passive"))
    )
    (net (code "253") (name "unconnected-(S68-C-PadK)") (class "Default")
      (node (ref "S68") (pin "K") (pinfunction "C_K") (pintype "passive"))
    )
    (net (code "254") (name "unconnected-(S68-PadA)") (class "Default")
      (node (ref "S68") (pin "A") (pinfunction "A_A") (pintype "passive"))
    )
    (net (code "255") (name "unconnected-(S69-C-PadK)") (class "Default")
      (node (ref "S69") (pin "K") (pinfunction "C_K") (pintype "passive"))
    )
    (net (code "256") (name "unconnected-(S69-PadA)") (class "Default")
      (node (ref "S69") (pin "A") (pinfunction "A_A") (pintype "passive"))
    )
    (net (code "257") (name "unconnected-(S70-C-PadK)") (class "Default")
      (node (ref "S70") (pin "K") (pinfunction "C_K") (pintype "passive"))
    )
    (net (code "258") (name "unconnected-(S70-PadA)") (class "Default")
      (node (ref "S70") (pin "A") (pinfunction "A_A") (pintype "passive"))
    )
    (net (code "259") (name "unconnected-(S71-C-PadK)") (class "Default")
      (node (ref "S71") (pin "K") (pinfunction "C_K") (pintype "passive"))
    )
    (net (code "260") (name "unconnected-(S71-PadA)") (class "Default")
      (node (ref "S71") (pin "A") (pinfunction "A_A") (pintype "passive"))
    )
    (net (code "261") (name "unconnected-(S72-C-PadK)") (class "Default")
      (node (ref "S72") (pin "K") (pinfunction "C_K") (pintype "passive"))
    )
    (net (code "262") (name "unconnected-(S72-PadA)") (class "Default")
      (node (ref "S72") (pin "A") (pinfunction "A_A") (pintype "passive"))
    )
    (net (code "263") (name "unconnected-(S73-C-PadK)") (class "Default")
      (node (ref "S73") (pin "K") (pinfunction "C_K") (pintype "passive"))
    )
    (net (code "264") (name "unconnected-(S73-PadA)") (class "Default")
      (node (ref "S73") (pin "A") (pinfunction "A_A") (pintype "passive"))
    )
    (net (code "265") (name "unconnected-(S74-C-PadK)") (class "Default")
      (node (ref "S74") (pin "K") (pinfunction "C_K") (pintype "passive"))
    )
    (net (code "266") (name "unconnected-(S74-PadA)") (class "Default")
      (node (ref "S74") (pin "A") (pinfunction "A_A") (pintype "passive"))
    )
    (net (code "267") (name "unconnected-(S75-C-PadK)") (class "Default")
      (node (ref "S75") (pin "K") (pinfunction "C_K") (pintype "passive"))
    )
    (net (code "268") (name "unconnected-(S75-PadA)") (class "Default")
      (node (ref "S75") (pin "A") (pinfunction "A_A") (pintype "passive"))
    )
    (net (code "269") (name "unconnected-(S76-C-PadK)") (class "Default")
      (node (ref "S76") (pin "K") (pinfunction "C_K") (pintype "passive"))
    )
    (net (code "270") (name "unconnected-(S76-PadA)") (class "Default")
      (node (ref "S76") (pin "A") (pinfunction "A_A") (pintype "passive"))
    )
    (net (code "271") (name "unconnected-(S77-C-PadK)") (class "Default")
      (node (ref "S77") (pin "K") (pinfunction "C_K") (pintype "passive"))
    )
    (net (code "272") (name "unconnected-(S77-PadA)") (class "Default")
      (node (ref "S77") (pin "A") (pinfunction "A_A") (pintype "passive"))
    )
    (net (code "273") (name "unconnected-(S78-C-PadK)") (class "Default")
      (node (ref "S78") (pin "K") (pinfunction "C_K") (pintype "passive"))
    )
    (net (code "274") (name "unconnected-(S78-PadA)") (class "Default")
      (node (ref "S78") (pin "A") (pinfunction "A_A") (pintype "passive"))
    )
    (net (code "275") (name "unconnected-(S79-C-PadK)") (class "Default")
      (node (ref "S79") (pin "K") (pinfunction "C_K") (pintype "passive"))
    )
    (net (code "276") (name "unconnected-(S79-PadA)") (class "Default")
      (node (ref "S79") (pin "A") (pinfunction "A_A") (pintype "passive"))
    )
    (net (code "277") (name "unconnected-(U$1-A8SBU1-PadA8)") (class "Default")
      (node (ref "U$1") (pin "A8") (pinfunction "A8SBU1_A8") (pintype "bidirectional"))
    )
    (net (code "278") (name "unconnected-(U$1-B8SBU2-PadB8)") (class "Default")
      (node (ref "U$1") (pin "B8") (pinfunction "B8SBU2_B8") (pintype "bidirectional"))
    )
  )
)
